# STM-Board-v1_0.net
KiCad netlist of a schematic drawn in Altium Designer
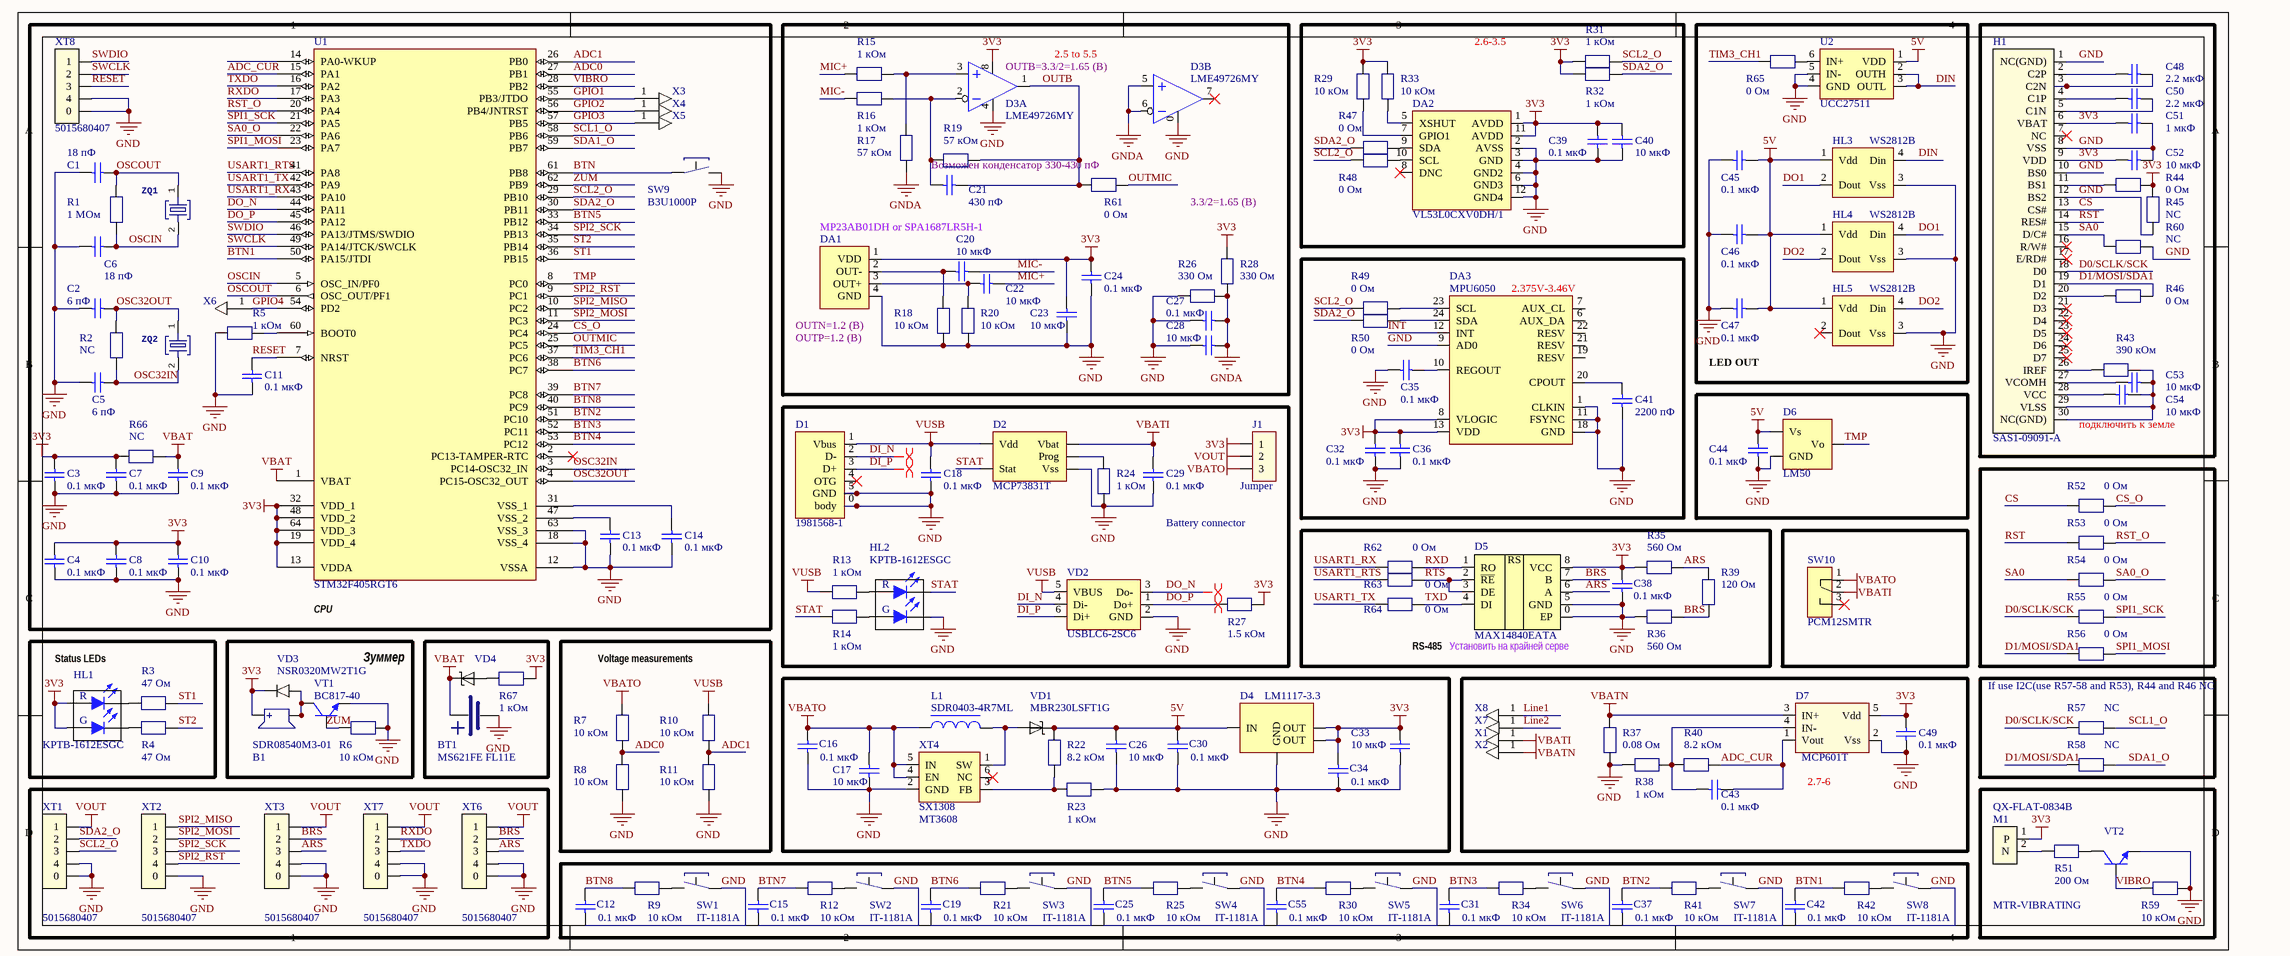
[diagram p0: STM-Board-v1.0.SchDoc]

(export (version "E")
  (design (tool "Eeschema 10.0.6"))
  (components
    (comp (ref "B1")
      (value "SDR08540M3-01")
      (footprint "SDR08540M3-01")
      (libsource (lib "dan") (part "SDR08540M3-01"))
    )
    (comp (ref "BT1")
      (value "MS621FE FL11E")
      (footprint "MS621FE FL11E")
      (libsource (lib "dan") (part "Battery RTC"))
    )
    (comp (ref "C1")
      (value "18 пФ")
      (footprint "C0402")
      (description "Чип конденсатор 0805")
      (fields (field (name "Comment") "Capacitor"))
      (libsource (lib "dan") (part "Capacitor"))
    )
    (comp (ref "C2")
      (value "6 пФ")
      (footprint "C0402")
      (description "Чип конденсатор 0805")
      (fields (field (name "Comment") "Capacitor"))
      (libsource (lib "dan") (part "Capacitor"))
    )
    (comp (ref "C3")
      (value "0.1 мкФ")
      (footprint "C0402")
      (description "Чип конденсатор 0805")
      (fields (field (name "Comment") "Capacitor"))
      (libsource (lib "dan") (part "Capacitor"))
    )
    (comp (ref "C4")
      (value "0.1 мкФ")
      (footprint "C0402")
      (description "Чип конденсатор 0805")
      (fields (field (name "Comment") "Capacitor"))
      (libsource (lib "dan") (part "Capacitor"))
    )
    (comp (ref "C5")
      (value "6 пФ")
      (footprint "C0402")
      (description "Чип конденсатор 0805")
      (fields (field (name "Comment") "Capacitor"))
      (libsource (lib "dan") (part "Capacitor"))
    )
    (comp (ref "C6")
      (value "18 пФ")
      (footprint "C0402")
      (description "Чип конденсатор 0805")
      (fields (field (name "Comment") "Capacitor"))
      (libsource (lib "dan") (part "Capacitor"))
    )
    (comp (ref "C7")
      (value "0.1 мкФ")
      (footprint "C0402")
      (description "Чип конденсатор 0805")
      (fields (field (name "Comment") "Capacitor"))
      (libsource (lib "dan") (part "Capacitor"))
    )
    (comp (ref "C8")
      (value "0.1 мкФ")
      (footprint "C0402")
      (description "Чип конденсатор 0805")
      (fields (field (name "Comment") "Capacitor"))
      (libsource (lib "dan") (part "Capacitor"))
    )
    (comp (ref "C9")
      (value "0.1 мкФ")
      (footprint "C0402")
      (description "Чип конденсатор 0805")
      (fields (field (name "Comment") "Capacitor"))
      (libsource (lib "dan") (part "Capacitor"))
    )
    (comp (ref "C10")
      (value "0.1 мкФ")
      (footprint "C0402")
      (description "Чип конденсатор 0805")
      (fields (field (name "Comment") "Capacitor"))
      (libsource (lib "dan") (part "Capacitor"))
    )
    (comp (ref "C11")
      (value "0.1 мкФ")
      (footprint "C0402")
      (description "Чип конденсатор 0805")
      (fields (field (name "Comment") "Capacitor"))
      (libsource (lib "dan") (part "Capacitor"))
    )
    (comp (ref "C12")
      (value "0.1 мкФ")
      (footprint "C0402")
      (description "Чип конденсатор 0805")
      (fields (field (name "Comment") "Capacitor"))
      (libsource (lib "dan") (part "Capacitor"))
    )
    (comp (ref "C13")
      (value "0.1 мкФ")
      (footprint "C0402")
      (description "Чип конденсатор 0805")
      (fields (field (name "Comment") "Capacitor"))
      (libsource (lib "dan") (part "Capacitor"))
    )
    (comp (ref "C14")
      (value "0.1 мкФ")
      (footprint "C0402")
      (description "Чип конденсатор 0805")
      (fields (field (name "Comment") "Capacitor"))
      (libsource (lib "dan") (part "Capacitor"))
    )
    (comp (ref "C15")
      (value "0.1 мкФ")
      (footprint "C0402")
      (description "Чип конденсатор 0805")
      (fields (field (name "Comment") "Capacitor"))
      (libsource (lib "dan") (part "Capacitor"))
    )
    (comp (ref "C16")
      (value "0.1 мкФ")
      (footprint "C0402")
      (description "Чип конденсатор 0805")
      (fields (field (name "Comment") "Capacitor"))
      (libsource (lib "dan") (part "Capacitor"))
    )
    (comp (ref "C17")
      (value "10 мкФ")
      (footprint "1206")
      (description "Чип конденсатор 0805")
      (fields (field (name "Comment") "Capacitor"))
      (libsource (lib "dan") (part "Capacitor"))
    )
    (comp (ref "C18")
      (value "0.1 мкФ")
      (footprint "C0402")
      (description "Чип конденсатор 0805")
      (fields (field (name "Comment") "Capacitor"))
      (libsource (lib "dan") (part "Capacitor"))
    )
    (comp (ref "C19")
      (value "0.1 мкФ")
      (footprint "C0402")
      (description "Чип конденсатор 0805")
      (fields (field (name "Comment") "Capacitor"))
      (libsource (lib "dan") (part "Capacitor"))
    )
    (comp (ref "C20")
      (value "10 мкФ")
      (footprint "C0402")
      (description "Чип конденсатор 0805")
      (fields (field (name "Comment") "Capacitor"))
      (libsource (lib "dan") (part "Capacitor"))
    )
    (comp (ref "C21")
      (value "430 пФ")
      (footprint "C0402")
      (description "Чип конденсатор 0805")
      (fields (field (name "Comment") "Capacitor"))
      (libsource (lib "dan") (part "Capacitor"))
    )
    (comp (ref "C22")
      (value "10 мкФ")
      (footprint "C0402")
      (description "Чип конденсатор 0805")
      (fields (field (name "Comment") "Capacitor"))
      (libsource (lib "dan") (part "Capacitor"))
    )
    (comp (ref "C23")
      (value "10 мкФ")
      (footprint "C0402")
      (description "Чип конденсатор 0805")
      (fields (field (name "Comment") "Capacitor"))
      (libsource (lib "dan") (part "Capacitor"))
    )
    (comp (ref "C24")
      (value "0.1 мкФ")
      (footprint "C0402")
      (description "Чип конденсатор 0805")
      (fields (field (name "Comment") "Capacitor"))
      (libsource (lib "dan") (part "Capacitor"))
    )
    (comp (ref "C25")
      (value "0.1 мкФ")
      (footprint "C0402")
      (description "Чип конденсатор 0805")
      (fields (field (name "Comment") "Capacitor"))
      (libsource (lib "dan") (part "Capacitor"))
    )
    (comp (ref "C26")
      (value "10 мкФ")
      (footprint "1206")
      (description "Чип конденсатор 0805")
      (fields (field (name "Comment") "Capacitor"))
      (libsource (lib "dan") (part "Capacitor"))
    )
    (comp (ref "C27")
      (value "0.1 мкФ")
      (footprint "C0402")
      (description "Чип конденсатор 0805")
      (fields (field (name "Comment") "Capacitor"))
      (libsource (lib "dan") (part "Capacitor"))
    )
    (comp (ref "C28")
      (value "10 мкФ")
      (footprint "C0402")
      (description "Чип конденсатор 0805")
      (fields (field (name "Comment") "Capacitor"))
      (libsource (lib "dan") (part "Capacitor"))
    )
    (comp (ref "C29")
      (value "0.1 мкФ")
      (footprint "C0402")
      (description "Чип конденсатор 0805")
      (fields (field (name "Comment") "Capacitor"))
      (libsource (lib "dan") (part "Capacitor"))
    )
    (comp (ref "C30")
      (value "0.1 мкФ")
      (footprint "C0402")
      (description "Чип конденсатор 0805")
      (fields (field (name "Comment") "Capacitor"))
      (libsource (lib "dan") (part "Capacitor"))
    )
    (comp (ref "C31")
      (value "0.1 мкФ")
      (footprint "C0402")
      (description "Чип конденсатор 0805")
      (fields (field (name "Comment") "Capacitor"))
      (libsource (lib "dan") (part "Capacitor"))
    )
    (comp (ref "C32")
      (value "0.1 мкФ")
      (footprint "C0402")
      (description "Чип конденсатор 0805")
      (fields (field (name "Comment") "Capacitor"))
      (libsource (lib "dan") (part "Capacitor"))
    )
    (comp (ref "C33")
      (value "10 мкФ")
      (footprint "1206")
      (description "Чип конденсатор 0805")
      (fields (field (name "Comment") "Capacitor"))
      (libsource (lib "dan") (part "Capacitor"))
    )
    (comp (ref "C34")
      (value "0.1 мкФ")
      (footprint "C0402")
      (description "Чип конденсатор 0805")
      (fields (field (name "Comment") "Capacitor"))
      (libsource (lib "dan") (part "Capacitor"))
    )
    (comp (ref "C35")
      (value "0.1 мкФ")
      (footprint "C0402")
      (description "Чип конденсатор 0805")
      (fields (field (name "Comment") "Capacitor"))
      (libsource (lib "dan") (part "Capacitor"))
    )
    (comp (ref "C36")
      (value "0.1 мкФ")
      (footprint "C0402")
      (description "Чип конденсатор 0805")
      (fields (field (name "Comment") "Capacitor"))
      (libsource (lib "dan") (part "Capacitor"))
    )
    (comp (ref "C37")
      (value "0.1 мкФ")
      (footprint "C0402")
      (description "Чип конденсатор 0805")
      (fields (field (name "Comment") "Capacitor"))
      (libsource (lib "dan") (part "Capacitor"))
    )
    (comp (ref "C38")
      (value "0.1 мкФ")
      (footprint "C0402")
      (description "Чип конденсатор 0805")
      (fields (field (name "Comment") "Capacitor"))
      (libsource (lib "dan") (part "Capacitor"))
    )
    (comp (ref "C39")
      (value "0.1 мкФ")
      (footprint "C0402")
      (description "Чип конденсатор 0805")
      (fields (field (name "Comment") "Capacitor"))
      (libsource (lib "dan") (part "Capacitor"))
    )
    (comp (ref "C40")
      (value "10 мкФ")
      (footprint "C0402")
      (description "Чип конденсатор 0805")
      (fields (field (name "Comment") "Capacitor"))
      (libsource (lib "dan") (part "Capacitor"))
    )
    (comp (ref "C41")
      (value "2200 пФ")
      (footprint "C0402")
      (description "Чип конденсатор 0805")
      (fields (field (name "Comment") "Capacitor"))
      (libsource (lib "dan") (part "Capacitor"))
    )
    (comp (ref "C42")
      (value "0.1 мкФ")
      (footprint "C0402")
      (description "Чип конденсатор 0805")
      (fields (field (name "Comment") "Capacitor"))
      (libsource (lib "dan") (part "Capacitor"))
    )
    (comp (ref "C43")
      (value "0.1 мкФ")
      (footprint "C0402")
      (description "Чип конденсатор 0805")
      (fields (field (name "Comment") "Capacitor"))
      (libsource (lib "dan") (part "Capacitor"))
    )
    (comp (ref "C44")
      (value "0.1 мкФ")
      (footprint "C0402")
      (description "Чип конденсатор 0805")
      (fields (field (name "Comment") "Capacitor"))
      (libsource (lib "dan") (part "Capacitor"))
    )
    (comp (ref "C45")
      (value "0.1 мкФ")
      (footprint "C0402")
      (description "Чип конденсатор 0805")
      (fields (field (name "Comment") "Capacitor"))
      (libsource (lib "dan") (part "Capacitor"))
    )
    (comp (ref "C46")
      (value "0.1 мкФ")
      (footprint "C0402")
      (description "Чип конденсатор 0805")
      (fields (field (name "Comment") "Capacitor"))
      (libsource (lib "dan") (part "Capacitor"))
    )
    (comp (ref "C47")
      (value "0.1 мкФ")
      (footprint "C0402")
      (description "Чип конденсатор 0805")
      (fields (field (name "Comment") "Capacitor"))
      (libsource (lib "dan") (part "Capacitor"))
    )
    (comp (ref "C48")
      (value "2.2 мкФ")
      (footprint "C0402")
      (description "Чип конденсатор 0805")
      (fields (field (name "Comment") "Capacitor"))
      (libsource (lib "dan") (part "Capacitor"))
    )
    (comp (ref "C49")
      (value "0.1 мкФ")
      (footprint "C0402")
      (description "Чип конденсатор 0805")
      (fields (field (name "Comment") "Capacitor"))
      (libsource (lib "dan") (part "Capacitor"))
    )
    (comp (ref "C50")
      (value "2.2 мкФ")
      (footprint "C0402")
      (description "Чип конденсатор 0805")
      (fields (field (name "Comment") "Capacitor"))
      (libsource (lib "dan") (part "Capacitor"))
    )
    (comp (ref "C51")
      (value "1 мкФ")
      (footprint "C0402")
      (description "Чип конденсатор 0805")
      (fields (field (name "Comment") "Capacitor"))
      (libsource (lib "dan") (part "Capacitor"))
    )
    (comp (ref "C52")
      (value "10 мкФ")
      (footprint "C0402")
      (description "Чип конденсатор 0805")
      (fields (field (name "Comment") "Capacitor"))
      (libsource (lib "dan") (part "Capacitor"))
    )
    (comp (ref "C53")
      (value "10 мкФ")
      (footprint "C0402")
      (description "Чип конденсатор 0805")
      (fields (field (name "Comment") "Capacitor"))
      (libsource (lib "dan") (part "Capacitor"))
    )
    (comp (ref "C54")
      (value "10 мкФ")
      (footprint "C0402")
      (description "Чип конденсатор 0805")
      (fields (field (name "Comment") "Capacitor"))
      (libsource (lib "dan") (part "Capacitor"))
    )
    (comp (ref "C55")
      (value "0.1 мкФ")
      (footprint "C0402")
      (description "Чип конденсатор 0805")
      (fields (field (name "Comment") "Capacitor"))
      (libsource (lib "dan") (part "Capacitor"))
    )
    (comp (ref "D1")
      (value "1981568-1")
      (footprint "MicroUSB-B")
      (description "micro")
      (libsource (lib "dan") (part "USB_micro"))
    )
    (comp (ref "D2") (value "MCP73831T") (footprint "SOT23-5") (libsource (lib "dan") (part "MCP73831")))
    (comp (ref "D3")
      (value "LME49726MY")
      (footprint "MSOP8 - PP")
      (description "Comparators")
      (fields (field (name "Comment") "Audio Operational Amplifier"))
      (libsource (lib "dan") (part "LME49726"))
    )
    (comp (ref "D4") (value "LM1117-3.3") (footprint "SOT223") (libsource (lib "dan") (part "LM1117")))
    (comp (ref "D5")
      (value "MAX14840EATA")
      (footprint "TDFN-8")
      (description "RS-485")
      (libsource (lib "dan") (part "MAX14840"))
    )
    (comp (ref "D6")
      (value "LM50")
      (footprint "SOT-23")
      (description "Temperatury sensors")
      (fields (field (name "Comment") "Датчик температуры"))
      (libsource (lib "dan") (part "LM50"))
    )
    (comp (ref "D7")
      (value "MCP601T")
      (footprint "SOT23-5")
      (fields (field (name "Comment") "Операционный усилитель"))
      (libsource (lib "dan") (part "MCP601T"))
    )
    (comp (ref "DA1")
      (value "MP23AB01DH or SPA1687LR5H-1")
      (footprint "MP23AB01DH")
      (libsource (lib "dan") (part "MP23AB01DH"))
    )
    (comp (ref "DA2")
      (value "VL53L0CXV0DH/1")
      (footprint "dan:VL53L0X - big")
      (fields (field (name "Comment") "ИК датчик VL53L0X"))
      (libsource (lib "dan") (part "VL53L0X"))
    )
    (comp (ref "DA3")
      (value "MPU6050")
      (footprint "MPU-6050")
      (fields (field (name "Comment") "Гироскоп"))
      (libsource (lib "dan") (part "MPU6050"))
    )
    (comp (ref "H1")
      (value "SAS1-09091-A")
      (footprint "OLED 1.3 128x64")
      (description "1.3in OLED 128x64  SAS1-09091-A")
      (fields (field (name "Comment") "OLED DIsp 1.3 128x64"))
      (libsource (lib "dan") (part "OLED_1.3_128x64"))
    )
    (comp (ref "HL1")
      (value "KPTB-1612ESGC")
      (footprint "LED_1.6x1.25")
      (libsource (lib "dan") (part "LED_x2_RG"))
    )
    (comp (ref "HL2")
      (value "KPTB-1612ESGC")
      (footprint "LED_1.6x1.25")
      (libsource (lib "dan") (part "LED_x2_RG"))
    )
    (comp (ref "HL3") (value "WS2812B") (footprint "WS2812B_N") (libsource (lib "dan") (part "WS2812B")))
    (comp (ref "HL4") (value "WS2812B") (footprint "WS2812B_N") (libsource (lib "dan") (part "WS2812B")))
    (comp (ref "HL5") (value "WS2812B") (footprint "WS2812B_N") (libsource (lib "dan") (part "WS2812B")))
    (comp (ref "J1")
      (value "Jumper")
      (footprint "Jumper_3")
      (fields (field (name "Comment") "Jumper_2"))
      (libsource (lib "dan") (part "Jumper_2"))
    )
    (comp (ref "L1") (value "SDR0403-4R7ML") (footprint "SDR0403") (libsource (lib "dan") (part "inductor")))
    (comp (ref "M1")
      (value "QX-FLAT-0834B")
      (footprint "QX-FLAT-0834B")
      (description "VIBRATING")
      (libsource (lib "dan") (part "QX-FLAT-0834B"))
    )
    (comp (ref "R1")
      (value "1 МОм")
      (footprint "R0402")
      (fields (field (name "Comment") "Чип резистор"))
      (libsource (lib "") (part "Resistor_2"))
    )
    (comp (ref "R2")
      (value "NC")
      (footprint "R0402")
      (fields (field (name "Comment") "Чип резистор"))
      (libsource (lib "") (part "Resistor_3"))
    )
    (comp (ref "R3")
      (value "47 Ом")
      (footprint "R0402")
      (fields (field (name "Comment") "Чип резистор 0402"))
      (libsource (lib "dan") (part "Resistor"))
    )
    (comp (ref "R4")
      (value "47 Ом")
      (footprint "R0402")
      (fields (field (name "Comment") "Чип резистор 0402"))
      (libsource (lib "dan") (part "Resistor"))
    )
    (comp (ref "R5")
      (value "1 кОм")
      (footprint "R0402")
      (fields (field (name "Comment") "Чип резистор"))
      (libsource (lib "") (part "Resistor_1"))
    )
    (comp (ref "R6")
      (value "10 кОм")
      (footprint "R0402")
      (fields (field (name "Comment") "Чип резистор"))
      (libsource (lib "") (part "Resistor_1"))
    )
    (comp (ref "R7")
      (value "10 кОм")
      (footprint "R0402")
      (fields (field (name "Comment") "Чип резистор"))
      (libsource (lib "") (part "Resistor_3"))
    )
    (comp (ref "R8")
      (value "10 кОм")
      (footprint "R0402")
      (fields (field (name "Comment") "Чип резистор"))
      (libsource (lib "") (part "Resistor_3"))
    )
    (comp (ref "R9")
      (value "10 кОм")
      (footprint "R0402")
      (fields (field (name "Comment") "Чип резистор"))
      (libsource (lib "dan") (part "Resistor"))
    )
    (comp (ref "R10")
      (value "10 кОм")
      (footprint "R0402")
      (fields (field (name "Comment") "Чип резистор"))
      (libsource (lib "") (part "Resistor_3"))
    )
    (comp (ref "R11")
      (value "10 кОм")
      (footprint "R0402")
      (fields (field (name "Comment") "Чип резистор"))
      (libsource (lib "") (part "Resistor_3"))
    )
    (comp (ref "R12")
      (value "10 кОм")
      (footprint "R0402")
      (fields (field (name "Comment") "Чип резистор"))
      (libsource (lib "dan") (part "Resistor"))
    )
    (comp (ref "R13")
      (value "1 кОм")
      (footprint "R0402")
      (description "Чип резистор 0402")
      (libsource (lib "dan") (part "R0402"))
    )
    (comp (ref "R14")
      (value "1 кОм")
      (footprint "R0402")
      (description "Чип резистор 0402")
      (libsource (lib "dan") (part "R0402"))
    )
    (comp (ref "R15")
      (value "1 кОм")
      (footprint "R0402")
      (fields (field (name "Comment") "Чип резистор"))
      (libsource (lib "dan") (part "Resistor"))
    )
    (comp (ref "R16")
      (value "1 кОм")
      (footprint "R0402")
      (fields (field (name "Comment") "Чип резистор"))
      (libsource (lib "dan") (part "Resistor"))
    )
    (comp (ref "R17")
      (value "57 кОм")
      (footprint "R0402")
      (fields (field (name "Comment") "Чип резистор"))
      (libsource (lib "") (part "Resistor_2"))
    )
    (comp (ref "R18")
      (value "10 кОм")
      (footprint "R0402")
      (fields (field (name "Comment") "Чип резистор"))
      (libsource (lib "") (part "Resistor_3"))
    )
    (comp (ref "R19")
      (value "57 кОм")
      (footprint "R0402")
      (fields (field (name "Comment") "Чип резистор"))
      (libsource (lib "dan") (part "Resistor"))
    )
    (comp (ref "R20")
      (value "10 кОм")
      (footprint "R0402")
      (fields (field (name "Comment") "Чип резистор"))
      (libsource (lib "") (part "Resistor_3"))
    )
    (comp (ref "R21")
      (value "10 кОм")
      (footprint "R0402")
      (fields (field (name "Comment") "Чип резистор"))
      (libsource (lib "dan") (part "Resistor"))
    )
    (comp (ref "R22")
      (value "8.2 кОм")
      (footprint "R0402")
      (description "Чип резистор 0402")
      (libsource (lib "") (part "R0402_1"))
    )
    (comp (ref "R23")
      (value "1 кОм")
      (footprint "R0402")
      (description "Чип резистор 0402")
      (libsource (lib "dan") (part "R0402"))
    )
    (comp (ref "R24")
      (value "1 кОм")
      (footprint "R0402")
      (fields (field (name "Comment") "Чип резистор"))
      (libsource (lib "") (part "Resistor_2"))
    )
    (comp (ref "R25")
      (value "10 кОм")
      (footprint "R0402")
      (fields (field (name "Comment") "Чип резистор"))
      (libsource (lib "dan") (part "Resistor"))
    )
    (comp (ref "R26")
      (value "330 Ом")
      (footprint "R0402")
      (fields (field (name "Comment") "Чип резистор"))
      (libsource (lib "dan") (part "Resistor"))
    )
    (comp (ref "R27")
      (value "1.5 кОм")
      (footprint "R0402")
      (fields (field (name "Comment") "Чип резистор"))
      (libsource (lib "dan") (part "Resistor"))
    )
    (comp (ref "R28")
      (value "330 Ом")
      (footprint "R0402")
      (fields (field (name "Comment") "Чип резистор"))
      (libsource (lib "") (part "Resistor_2"))
    )
    (comp (ref "R29")
      (value "10 кОм")
      (footprint "R0402")
      (fields (field (name "Comment") "Чип резистор"))
      (libsource (lib "") (part "Resistor_2"))
    )
    (comp (ref "R30")
      (value "10 кОм")
      (footprint "R0402")
      (fields (field (name "Comment") "Чип резистор"))
      (libsource (lib "dan") (part "Resistor"))
    )
    (comp (ref "R31")
      (value "1 кОм")
      (footprint "R0402")
      (fields (field (name "Comment") "Чип резистор"))
      (libsource (lib "") (part "Resistor_1"))
    )
    (comp (ref "R32")
      (value "1 кОм")
      (footprint "R0402")
      (fields (field (name "Comment") "Чип резистор"))
      (libsource (lib "") (part "Resistor_1"))
    )
    (comp (ref "R33")
      (value "10 кОм")
      (footprint "R0402")
      (fields (field (name "Comment") "Чип резистор"))
      (libsource (lib "") (part "Resistor_2"))
    )
    (comp (ref "R34")
      (value "10 кОм")
      (footprint "R0402")
      (fields (field (name "Comment") "Чип резистор"))
      (libsource (lib "dan") (part "Resistor"))
    )
    (comp (ref "R35")
      (value "560 Ом")
      (footprint "R0402")
      (fields (field (name "Comment") "Чип резистор"))
      (libsource (lib "") (part "Resistor_1"))
    )
    (comp (ref "R36")
      (value "560 Ом")
      (footprint "R0402")
      (fields (field (name "Comment") "Чип резистор"))
      (libsource (lib "") (part "Resistor_1"))
    )
    (comp (ref "R37")
      (value "0.08 Ом")
      (footprint "P1206")
      (fields (field (name "Comment") "Чип резистор"))
      (libsource (lib "") (part "Resistor_3"))
    )
    (comp (ref "R38")
      (value "1 кОм")
      (footprint "R0402")
      (fields (field (name "Comment") "Чип резистор"))
      (libsource (lib "") (part "Resistor_1"))
    )
    (comp (ref "R39")
      (value "120 Ом")
      (footprint "R0402")
      (fields (field (name "Comment") "Чип резистор"))
      (libsource (lib "") (part "Resistor_3"))
    )
    (comp (ref "R40")
      (value "8.2 кОм")
      (footprint "R0402")
      (fields (field (name "Comment") "Чип резистор"))
      (libsource (lib "") (part "Resistor_1"))
    )
    (comp (ref "R41")
      (value "10 кОм")
      (footprint "R0402")
      (fields (field (name "Comment") "Чип резистор"))
      (libsource (lib "dan") (part "Resistor"))
    )
    (comp (ref "R42")
      (value "10 кОм")
      (footprint "R0402")
      (fields (field (name "Comment") "Чип резистор"))
      (libsource (lib "dan") (part "Resistor"))
    )
    (comp (ref "R43")
      (value "390 кОм")
      (footprint "R0402")
      (fields (field (name "Comment") "Чип резистор"))
      (libsource (lib "") (part "Resistor_1"))
    )
    (comp (ref "R44")
      (value "0 Ом")
      (footprint "R0402")
      (fields (field (name "Comment") "Чип резистор"))
      (libsource (lib "") (part "Resistor_1"))
    )
    (comp (ref "R45")
      (value "NC")
      (footprint "R0402")
      (fields (field (name "Comment") "Чип резистор"))
      (libsource (lib "") (part "Resistor_3"))
    )
    (comp (ref "R46")
      (value "0 Ом")
      (footprint "R0402")
      (fields (field (name "Comment") "Чип резистор"))
      (libsource (lib "") (part "Resistor_1"))
    )
    (comp (ref "R47")
      (value "0 Ом")
      (footprint "R0402")
      (fields (field (name "Comment") "Чип резистор"))
      (libsource (lib "") (part "Resistor_1"))
    )
    (comp (ref "R48")
      (value "0 Ом")
      (footprint "R0402")
      (fields (field (name "Comment") "Чип резистор"))
      (libsource (lib "") (part "Resistor_1"))
    )
    (comp (ref "R49")
      (value "0 Ом")
      (footprint "R0402")
      (fields (field (name "Comment") "Чип резистор"))
      (libsource (lib "") (part "Resistor_1"))
    )
    (comp (ref "R50")
      (value "0 Ом")
      (footprint "R0402")
      (fields (field (name "Comment") "Чип резистор"))
      (libsource (lib "") (part "Resistor_1"))
    )
    (comp (ref "R51")
      (value "200 Ом")
      (footprint "R0402")
      (fields (field (name "Comment") "Чип резистор"))
      (libsource (lib "dan") (part "Resistor"))
    )
    (comp (ref "R52")
      (value "0 Ом")
      (footprint "R0402")
      (fields (field (name "Comment") "Чип резистор"))
      (libsource (lib "") (part "Resistor_1"))
    )
    (comp (ref "R53")
      (value "0 Ом")
      (footprint "R0402")
      (fields (field (name "Comment") "Чип резистор"))
      (libsource (lib "") (part "Resistor_1"))
    )
    (comp (ref "R54")
      (value "0 Ом")
      (footprint "R0402")
      (fields (field (name "Comment") "Чип резистор"))
      (libsource (lib "") (part "Resistor_1"))
    )
    (comp (ref "R55")
      (value "0 Ом")
      (footprint "R0402")
      (fields (field (name "Comment") "Чип резистор"))
      (libsource (lib "") (part "Resistor_1"))
    )
    (comp (ref "R56")
      (value "0 Ом")
      (footprint "R0402")
      (fields (field (name "Comment") "Чип резистор"))
      (libsource (lib "") (part "Resistor_1"))
    )
    (comp (ref "R57")
      (value "NC")
      (footprint "R0402")
      (fields (field (name "Comment") "Чип резистор"))
      (libsource (lib "") (part "Resistor_1"))
    )
    (comp (ref "R58")
      (value "NC")
      (footprint "R0402")
      (fields (field (name "Comment") "Чип резистор"))
      (libsource (lib "") (part "Resistor_1"))
    )
    (comp (ref "R59")
      (value "10 кОм")
      (footprint "R0402")
      (fields (field (name "Comment") "Чип резистор"))
      (libsource (lib "dan") (part "Resistor"))
    )
    (comp (ref "R60")
      (value "NC")
      (footprint "R0402")
      (fields (field (name "Comment") "Чип резистор"))
      (libsource (lib "") (part "Resistor_1"))
    )
    (comp (ref "R61")
      (value "0 Ом")
      (footprint "R0402")
      (fields (field (name "Comment") "Чип резистор"))
      (libsource (lib "") (part "Resistor_1"))
    )
    (comp (ref "R62")
      (value "0 Ом")
      (footprint "R0402")
      (fields (field (name "Comment") "Чип резистор"))
      (libsource (lib "") (part "Resistor_1"))
    )
    (comp (ref "R63")
      (value "0 Ом")
      (footprint "R0402")
      (fields (field (name "Comment") "Чип резистор"))
      (libsource (lib "") (part "Resistor_1"))
    )
    (comp (ref "R64")
      (value "0 Ом")
      (footprint "R0402")
      (fields (field (name "Comment") "Чип резистор"))
      (libsource (lib "") (part "Resistor_1"))
    )
    (comp (ref "R65")
      (value "0 Ом")
      (footprint "R0402")
      (fields (field (name "Comment") "Чип резистор"))
      (libsource (lib "") (part "Resistor_1"))
    )
    (comp (ref "R66")
      (value "NC")
      (footprint "R0402")
      (fields (field (name "Comment") "Чип резистор"))
      (libsource (lib "dan") (part "Resistor"))
    )
    (comp (ref "R67")
      (value "1 кОм")
      (footprint "R0402")
      (fields (field (name "Comment") "Чип резистор"))
      (libsource (lib "") (part "Resistor_1"))
    )
    (comp (ref "SW1") (value "IT-1181A") (footprint "SWT-1") (libsource (lib "dan") (part "SWT-1-1")))
    (comp (ref "SW2") (value "IT-1181A") (footprint "SWT-1") (libsource (lib "dan") (part "SWT-1-1")))
    (comp (ref "SW3") (value "IT-1181A") (footprint "SWT-1") (libsource (lib "dan") (part "SWT-1-1")))
    (comp (ref "SW4") (value "IT-1181A") (footprint "SWT-1") (libsource (lib "dan") (part "SWT-1-1")))
    (comp (ref "SW5") (value "IT-1181A") (footprint "SWT-1") (libsource (lib "dan") (part "SWT-1-1")))
    (comp (ref "SW6") (value "IT-1181A") (footprint "SWT-1") (libsource (lib "dan") (part "SWT-1-1")))
    (comp (ref "SW7") (value "IT-1181A") (footprint "SWT-1") (libsource (lib "dan") (part "SWT-1-1")))
    (comp (ref "SW8") (value "IT-1181A") (footprint "SWT-1") (libsource (lib "dan") (part "SWT-1-1")))
    (comp (ref "SW9") (value "B3U1000P") (footprint "B3U1000P") (libsource (lib "dan") (part "SWT-1_1")))
    (comp (ref "SW10") (value "PCM12SMTR") (footprint "PCM12SMTR") (libsource (lib "dan") (part "PCM12SMTR")))
    (comp (ref "U1")
      (value "STM32F405RGT6")
      (footprint "LQFP64_L")
      (description "STM32 ARM-Cortex M3 32-bit MCU, 128 kB")
      (fields (field (name "Comment") "STM32F302RCT6"))
      (libsource (lib "dan") (part "STM32F302R"))
    )
    (comp (ref "U2") (value "UCC27511") (footprint "SOT23-6") (libsource (lib "dan") (part "UCC27511")))
    (comp (ref "VD1")
      (value "MBR230LSFT1G")
      (footprint "SOD-123")
      (description "Diod schottki")
      (libsource (lib "dan") (part "MBR120LSFT1G"))
    )
    (comp (ref "VD2")
      (value "USBLC6-2SC6")
      (footprint "SOT23-6")
      (description "ESD")
      (libsource (lib "dan") (part "USBLC6-2SC6"))
    )
    (comp (ref "VD3")
      (value "NSR0320MW2T1G")
      (footprint "SOD-323")
      (description "Диод")
      (libsource (lib "dan") (part "diode"))
    )
    (comp (ref "VD4")
      (value "NSR0320MW2T1G")
      (footprint "SOD-323")
      (description "Diod schottki")
      (libsource (lib "dan") (part "MBR120LSFT1G"))
    )
    (comp (ref "VT1")
      (value "ВС817-40")
      (footprint "SOT-23")
      (description "BC817-40 NPN Транзистор")
      (libsource (lib "dan") (part "BC817-40"))
    )
    (comp (ref "VT2")
      (value "ВС817-40")
      (footprint "SOT-23")
      (description "BC817-40 NPN Транзистор")
      (libsource (lib "dan") (part "BC817-40"))
    )
    (comp (ref "X1") (value "~") (footprint "PAD_1X2") (libsource (lib "dan") (part "Pad")))
    (comp (ref "X2") (value "~") (footprint "PAD_1X2") (libsource (lib "dan") (part "Pad")))
    (comp (ref "X3") (value "~") (footprint "Pad_R2") (libsource (lib "dan") (part "Pad")))
    (comp (ref "X4") (value "~") (footprint "Pad_R2") (libsource (lib "dan") (part "Pad")))
    (comp (ref "X5") (value "~") (footprint "Pad_R2") (libsource (lib "dan") (part "Pad")))
    (comp (ref "X6") (value "~") (footprint "Pad_R2") (libsource (lib "dan") (part "Pad")))
    (comp (ref "X7") (value "~") (footprint "Pad_R2") (libsource (lib "dan") (part "Pad")))
    (comp (ref "X8") (value "~") (footprint "Pad_R2") (libsource (lib "dan") (part "Pad")))
    (comp (ref "XT1")
      (value "5015680407")
      (footprint "5015680407")
      (description "molex")
      (libsource (lib "dan") (part "5015680407"))
    )
    (comp (ref "XT2")
      (value "5015680407")
      (footprint "5015680407")
      (description "molex")
      (libsource (lib "dan") (part "5015680407"))
    )
    (comp (ref "XT3")
      (value "5015680407")
      (footprint "5015680407")
      (description "molex")
      (libsource (lib "dan") (part "5015680407"))
    )
    (comp (ref "XT4")
      (value "SX1308")
      (footprint "SOT23-6")
      (description "DC-DC Step_Up")
      (libsource (lib "dan") (part "SX1308"))
    )
    (comp (ref "XT6")
      (value "5015680407")
      (footprint "5015680407")
      (description "molex")
      (libsource (lib "dan") (part "5015680407"))
    )
    (comp (ref "XT7")
      (value "5015680407")
      (footprint "5015680407")
      (description "molex")
      (libsource (lib "dan") (part "5015680407"))
    )
    (comp (ref "XT8")
      (value "5015680407")
      (footprint "5015680407")
      (description "molex")
      (libsource (lib "dan") (part "5015680407"))
    )
    (comp (ref "ZQ1")
      (value "ABM3-8.000MHZ-D2Y-T")
      (footprint "ABM3")
      (description "SMD Quartz")
      (libsource (lib "dan") (part "ABM3"))
    )
    (comp (ref "ZQ2")
      (value "ABS07-120-32.768KHZ-T")
      (footprint "ABS07")
      (description "SMD Quartz")
      (libsource (lib "dan") (part "ABM3"))
    )
  )
  (nets
    (net (code "1") (name "/ADC0") (class "Default")
      (node (ref "R7") (pin "2") (pinfunction "2_2") (pintype "passive"))
      (node (ref "R8") (pin "1") (pinfunction "1_1") (pintype "passive"))
      (node (ref "U1") (pin "27") (pinfunction "PB1_27") (pintype "bidirectional"))
    )
    (net (code "2") (name "/ADC1") (class "Default")
      (node (ref "R10") (pin "2") (pinfunction "2_2") (pintype "passive"))
      (node (ref "R11") (pin "1") (pinfunction "1_1") (pintype "passive"))
      (node (ref "U1") (pin "26") (pinfunction "PB0_26") (pintype "bidirectional"))
    )
    (net (code "3") (name "/ADC_CUR") (class "Default")
      (node (ref "C43") (pin "1") (pinfunction "1_1") (pintype "passive"))
      (node (ref "D7") (pin "1") (pinfunction "Vout_1") (pintype "passive"))
      (node (ref "R40") (pin "1") (pinfunction "1_1") (pintype "passive"))
      (node (ref "U1") (pin "15") (pinfunction "PA1_15") (pintype "bidirectional"))
    )
    (net (code "4") (name "/ARS") (class "Default")
      (node (ref "D5") (pin "6") (pinfunction "A_6") (pintype "passive"))
      (node (ref "R35") (pin "1") (pinfunction "1_1") (pintype "passive"))
      (node (ref "R39") (pin "1") (pinfunction "1_1") (pintype "passive"))
      (node (ref "XT3") (pin "3") (pinfunction "3_3") (pintype "passive"))
      (node (ref "XT6") (pin "3") (pinfunction "3_3") (pintype "passive"))
    )
    (net (code "5") (name "/BRS") (class "Default")
      (node (ref "D5") (pin "7") (pinfunction "B_7") (pintype "passive"))
      (node (ref "R36") (pin "1") (pinfunction "1_1") (pintype "passive"))
      (node (ref "R39") (pin "2") (pinfunction "2_2") (pintype "passive"))
      (node (ref "XT3") (pin "2") (pinfunction "2_2") (pintype "passive"))
      (node (ref "XT6") (pin "2") (pinfunction "2_2") (pintype "passive"))
    )
    (net (code "6") (name "/BTN") (class "Default")
      (node (ref "SW9") (pin "1") (pinfunction "1_1") (pintype "passive"))
      (node (ref "U1") (pin "61") (pinfunction "PB8_61") (pintype "bidirectional"))
    )
    (net (code "7") (name "/BTN1") (class "Default")
      (node (ref "C42") (pin "2") (pinfunction "2_2") (pintype "passive"))
      (node (ref "R42") (pin "1") (pinfunction "1_1") (pintype "passive"))
      (node (ref "U1") (pin "50") (pinfunction "PA15/JTDI_50") (pintype "bidirectional"))
    )
    (net (code "8") (name "/BTN2") (class "Default")
      (node (ref "C37") (pin "2") (pinfunction "2_2") (pintype "passive"))
      (node (ref "R41") (pin "1") (pinfunction "1_1") (pintype "passive"))
      (node (ref "U1") (pin "51") (pinfunction "PC10_51") (pintype "bidirectional"))
    )
    (net (code "9") (name "/BTN3") (class "Default")
      (node (ref "C31") (pin "2") (pinfunction "2_2") (pintype "passive"))
      (node (ref "R34") (pin "1") (pinfunction "1_1") (pintype "passive"))
      (node (ref "U1") (pin "52") (pinfunction "PC11_52") (pintype "bidirectional"))
    )
    (net (code "10") (name "/BTN4") (class "Default")
      (node (ref "C55") (pin "2") (pinfunction "2_2") (pintype "passive"))
      (node (ref "R30") (pin "1") (pinfunction "1_1") (pintype "passive"))
      (node (ref "U1") (pin "53") (pinfunction "PC12_53") (pintype "bidirectional"))
    )
    (net (code "11") (name "/BTN5") (class "Default")
      (node (ref "C25") (pin "2") (pinfunction "2_2") (pintype "passive"))
      (node (ref "R25") (pin "1") (pinfunction "1_1") (pintype "passive"))
      (node (ref "U1") (pin "33") (pinfunction "PB12_33") (pintype "bidirectional"))
    )
    (net (code "12") (name "/BTN6") (class "Default")
      (node (ref "C19") (pin "2") (pinfunction "2_2") (pintype "passive"))
      (node (ref "R21") (pin "1") (pinfunction "1_1") (pintype "passive"))
      (node (ref "U1") (pin "38") (pinfunction "PC7_38") (pintype "bidirectional"))
    )
    (net (code "13") (name "/BTN7") (class "Default")
      (node (ref "C15") (pin "2") (pinfunction "2_2") (pintype "passive"))
      (node (ref "R12") (pin "1") (pinfunction "1_1") (pintype "passive"))
      (node (ref "U1") (pin "39") (pinfunction "PC8_39") (pintype "bidirectional"))
    )
    (net (code "14") (name "/BTN8") (class "Default")
      (node (ref "C12") (pin "2") (pinfunction "2_2") (pintype "passive"))
      (node (ref "R9") (pin "1") (pinfunction "1_1") (pintype "passive"))
      (node (ref "U1") (pin "40") (pinfunction "PC9_40") (pintype "bidirectional"))
    )
    (net (code "15") (name "/CS") (class "Default")
      (node (ref "H1") (pin "13") (pinfunction "CS#_13") (pintype "passive"))
      (node (ref "R52") (pin "2") (pinfunction "2_2") (pintype "passive"))
    )
    (net (code "16") (name "/CS_O") (class "Default")
      (node (ref "R52") (pin "1") (pinfunction "1_1") (pintype "passive"))
      (node (ref "U1") (pin "24") (pinfunction "PC4_24") (pintype "bidirectional"))
    )
    (net (code "17") (name "/D0{slash}SCLK{slash}SCK") (class "Default")
      (node (ref "H1") (pin "18") (pinfunction "D0_18") (pintype "passive"))
      (node (ref "R55") (pin "2") (pinfunction "2_2") (pintype "passive"))
      (node (ref "R57") (pin "2") (pinfunction "2_2") (pintype "passive"))
    )
    (net (code "18") (name "/D1{slash}MOSI{slash}SDA1") (class "Default")
      (node (ref "H1") (pin "19") (pinfunction "D1_19") (pintype "passive"))
      (node (ref "R46") (pin "1") (pinfunction "1_1") (pintype "passive"))
      (node (ref "R56") (pin "2") (pinfunction "2_2") (pintype "passive"))
      (node (ref "R58") (pin "2") (pinfunction "2_2") (pintype "passive"))
    )
    (net (code "19") (name "/DIN") (class "Default")
      (node (ref "HL3") (pin "4") (pinfunction "Din_4") (pintype "passive"))
      (node (ref "U2") (pin "2") (pinfunction "OUTH_2") (pintype "power_in"))
      (node (ref "U2") (pin "3") (pinfunction "OUTL_3") (pintype "power_in"))
    )
    (net (code "20") (name "/DI_N") (class "Default")
      (node (ref "D1") (pin "2") (pinfunction "D-_2") (pintype "passive"))
      (node (ref "VD2") (pin "4") (pinfunction "Di-_4") (pintype "power_in"))
    )
    (net (code "21") (name "/DI_P") (class "Default")
      (node (ref "D1") (pin "3") (pinfunction "D+_3") (pintype "passive"))
      (node (ref "VD2") (pin "6") (pinfunction "Di+_6") (pintype "passive"))
    )
    (net (code "22") (name "/DO1") (class "Default")
      (node (ref "HL3") (pin "2") (pinfunction "Dout_2") (pintype "passive"))
      (node (ref "HL4") (pin "4") (pinfunction "Din_4") (pintype "passive"))
    )
    (net (code "23") (name "/DO2") (class "Default")
      (node (ref "HL4") (pin "2") (pinfunction "Dout_2") (pintype "passive"))
      (node (ref "HL5") (pin "4") (pinfunction "Din_4") (pintype "passive"))
    )
    (net (code "24") (name "/DO_N") (class "Default")
      (node (ref "U1") (pin "44") (pinfunction "PA11_44") (pintype "bidirectional"))
      (node (ref "VD2") (pin "3") (pinfunction "Do-_3") (pintype "power_in"))
    )
    (net (code "25") (name "/DO_P") (class "Default")
      (node (ref "R27") (pin "1") (pinfunction "1_1") (pintype "passive"))
      (node (ref "U1") (pin "45") (pinfunction "PA12_45") (pintype "bidirectional"))
      (node (ref "VD2") (pin "1") (pinfunction "Do+_1") (pintype "power_in"))
    )
    (net (code "26") (name "/GPIO1") (class "Default")
      (node (ref "U1") (pin "55") (pinfunction "PB3/JTDO_55") (pintype "bidirectional"))
      (node (ref "X3") (pin "1") (pinfunction "1_1") (pintype "passive"))
    )
    (net (code "27") (name "/GPIO2") (class "Default")
      (node (ref "U1") (pin "56") (pinfunction "PB4/JNTRST_56") (pintype "bidirectional"))
      (node (ref "X4") (pin "1") (pinfunction "1_1") (pintype "passive"))
    )
    (net (code "28") (name "/GPIO3") (class "Default")
      (node (ref "U1") (pin "57") (pinfunction "PB5_57") (pintype "bidirectional"))
      (node (ref "X5") (pin "1") (pinfunction "1_1") (pintype "passive"))
    )
    (net (code "29") (name "/GPIO4") (class "Default")
      (node (ref "U1") (pin "54") (pinfunction "PD2_54") (pintype "bidirectional"))
      (node (ref "X6") (pin "1") (pinfunction "1_1") (pintype "passive"))
    )
    (net (code "30") (name "/INT") (class "Default")
      (node (ref "DA3") (pin "12") (pinfunction "INT_12") (pintype "passive"))
    )
    (net (code "31") (name "/Line1") (class "Default")
      (node (ref "X8") (pin "1") (pinfunction "1_1") (pintype "passive"))
    )
    (net (code "32") (name "/Line2") (class "Default")
      (node (ref "X7") (pin "1") (pinfunction "1_1") (pintype "passive"))
    )
    (net (code "33") (name "/MIC+") (class "Default")
      (node (ref "C22") (pin "1") (pinfunction "1_1") (pintype "passive"))
      (node (ref "R15") (pin "1") (pinfunction "1_1") (pintype "passive"))
    )
    (net (code "34") (name "/MIC-") (class "Default")
      (node (ref "C20") (pin "1") (pinfunction "1_1") (pintype "passive"))
      (node (ref "R16") (pin "1") (pinfunction "1_1") (pintype "passive"))
    )
    (net (code "35") (name "/OSC32IN") (class "Default")
      (node (ref "C5") (pin "2") (pinfunction "2_2") (pintype "passive"))
      (node (ref "R2") (pin "2") (pinfunction "2_2") (pintype "passive"))
      (node (ref "U1") (pin "3") (pinfunction "PC14-OSC32_IN_3") (pintype "bidirectional"))
      (node (ref "ZQ2") (pin "2") (pinfunction "2_2") (pintype "passive"))
    )
    (net (code "36") (name "/OSC32OUT") (class "Default")
      (node (ref "C2") (pin "2") (pinfunction "2_2") (pintype "passive"))
      (node (ref "R2") (pin "1") (pinfunction "1_1") (pintype "passive"))
      (node (ref "U1") (pin "4") (pinfunction "PC15-OSC32_OUT_4") (pintype "bidirectional"))
      (node (ref "ZQ2") (pin "1") (pinfunction "1_1") (pintype "passive"))
    )
    (net (code "37") (name "/OSCIN") (class "Default")
      (node (ref "C6") (pin "2") (pinfunction "2_2") (pintype "passive"))
      (node (ref "R1") (pin "1") (pinfunction "1_1") (pintype "passive"))
      (node (ref "U1") (pin "5") (pinfunction "OSC_IN/PF0_5") (pintype "input"))
      (node (ref "ZQ1") (pin "2") (pinfunction "2_2") (pintype "passive"))
    )
    (net (code "38") (name "/OSCOUT") (class "Default")
      (node (ref "C1") (pin "2") (pinfunction "2_2") (pintype "passive"))
      (node (ref "R1") (pin "2") (pinfunction "2_2") (pintype "passive"))
      (node (ref "U1") (pin "6") (pinfunction "OSC_OUT/PF1_6") (pintype "output"))
      (node (ref "ZQ1") (pin "1") (pinfunction "1_1") (pintype "passive"))
    )
    (net (code "39") (name "/OUTB") (class "Default")
      (node (ref "C21") (pin "1") (pinfunction "1_1") (pintype "passive"))
      (node (ref "D3") (pin "1") (pinfunction "1OUT_1") (pintype "passive"))
      (node (ref "R19") (pin "2") (pinfunction "2_2") (pintype "passive"))
      (node (ref "R61") (pin "2") (pinfunction "2_2") (pintype "passive"))
    )
    (net (code "40") (name "/OUTMIC") (class "Default")
      (node (ref "R61") (pin "1") (pinfunction "1_1") (pintype "passive"))
      (node (ref "U1") (pin "25") (pinfunction "PC5_25") (pintype "bidirectional"))
    )
    (net (code "41") (name "/RESET") (class "Default")
      (node (ref "C11") (pin "1") (pinfunction "1_1") (pintype "passive"))
      (node (ref "U1") (pin "7") (pinfunction "NRST_7") (pintype "bidirectional"))
      (node (ref "XT8") (pin "3") (pinfunction "3_3") (pintype "passive"))
    )
    (net (code "42") (name "/RST") (class "Default")
      (node (ref "H1") (pin "14") (pinfunction "RES#_14") (pintype "passive"))
      (node (ref "R53") (pin "2") (pinfunction "2_2") (pintype "passive"))
    )
    (net (code "43") (name "/RST_O") (class "Default")
      (node (ref "R53") (pin "1") (pinfunction "1_1") (pintype "passive"))
      (node (ref "U1") (pin "20") (pinfunction "PA4_20") (pintype "bidirectional"))
    )
    (net (code "44") (name "/RTS") (class "Default")
      (node (ref "D5") (pin "2") (pinfunction "~{RE}_2") (pintype "passive"))
      (node (ref "D5") (pin "3") (pinfunction "DE_3") (pintype "passive"))
      (node (ref "R63") (pin "1") (pinfunction "1_1") (pintype "passive"))
    )
    (net (code "45") (name "/RXD") (class "Default")
      (node (ref "D5") (pin "1") (pinfunction "RO_1") (pintype "passive"))
      (node (ref "R62") (pin "1") (pinfunction "1_1") (pintype "passive"))
    )
    (net (code "46") (name "/RXDO") (class "Default")
      (node (ref "U1") (pin "17") (pinfunction "PA3_17") (pintype "bidirectional"))
      (node (ref "XT7") (pin "2") (pinfunction "2_2") (pintype "passive"))
    )
    (net (code "47") (name "/SA0") (class "Default")
      (node (ref "H1") (pin "15") (pinfunction "D/C#_15") (pintype "passive"))
      (node (ref "R54") (pin "2") (pinfunction "2_2") (pintype "passive"))
      (node (ref "R60") (pin "2") (pinfunction "2_2") (pintype "passive"))
    )
    (net (code "48") (name "/SA0_O") (class "Default")
      (node (ref "R54") (pin "1") (pinfunction "1_1") (pintype "passive"))
      (node (ref "U1") (pin "22") (pinfunction "PA6_22") (pintype "bidirectional"))
    )
    (net (code "49") (name "/SCL1_O") (class "Default")
      (node (ref "R57") (pin "1") (pinfunction "1_1") (pintype "passive"))
      (node (ref "U1") (pin "58") (pinfunction "PB6_58") (pintype "bidirectional"))
    )
    (net (code "50") (name "/SCL2_O") (class "Default")
      (node (ref "R31") (pin "1") (pinfunction "1_1") (pintype "passive"))
      (node (ref "R48") (pin "2") (pinfunction "2_2") (pintype "passive"))
      (node (ref "R49") (pin "2") (pinfunction "2_2") (pintype "passive"))
      (node (ref "U1") (pin "29") (pinfunction "PB10_29") (pintype "bidirectional"))
      (node (ref "XT1") (pin "3") (pinfunction "3_3") (pintype "passive"))
    )
    (net (code "51") (name "/SDA1_O") (class "Default")
      (node (ref "R58") (pin "1") (pinfunction "1_1") (pintype "passive"))
      (node (ref "U1") (pin "59") (pinfunction "PB7_59") (pintype "bidirectional"))
    )
    (net (code "52") (name "/SDA2_O") (class "Default")
      (node (ref "R32") (pin "1") (pinfunction "1_1") (pintype "passive"))
      (node (ref "R47") (pin "2") (pinfunction "2_2") (pintype "passive"))
      (node (ref "R50") (pin "2") (pinfunction "2_2") (pintype "passive"))
      (node (ref "U1") (pin "30") (pinfunction "PB11_30") (pintype "bidirectional"))
      (node (ref "XT1") (pin "2") (pinfunction "2_2") (pintype "passive"))
    )
    (net (code "53") (name "/SPI1_MOSI") (class "Default")
      (node (ref "R56") (pin "1") (pinfunction "1_1") (pintype "passive"))
      (node (ref "U1") (pin "23") (pinfunction "PA7_23") (pintype "bidirectional"))
    )
    (net (code "54") (name "/SPI1_SCK") (class "Default")
      (node (ref "R55") (pin "1") (pinfunction "1_1") (pintype "passive"))
      (node (ref "U1") (pin "21") (pinfunction "PA5_21") (pintype "bidirectional"))
    )
    (net (code "55") (name "/SPI2_MISO") (class "Default")
      (node (ref "U1") (pin "10") (pinfunction "PC2_10") (pintype "bidirectional"))
      (node (ref "XT2") (pin "1") (pinfunction "1_1") (pintype "passive"))
    )
    (net (code "56") (name "/SPI2_MOSI") (class "Default")
      (node (ref "U1") (pin "11") (pinfunction "PC3_11") (pintype "bidirectional"))
      (node (ref "XT2") (pin "2") (pinfunction "2_2") (pintype "passive"))
    )
    (net (code "57") (name "/SPI2_RST") (class "Default")
      (node (ref "U1") (pin "9") (pinfunction "PC1_9") (pintype "bidirectional"))
      (node (ref "XT2") (pin "4") (pinfunction "4_4") (pintype "passive"))
    )
    (net (code "58") (name "/SPI2_SCK") (class "Default")
      (node (ref "U1") (pin "34") (pinfunction "PB13_34") (pintype "bidirectional"))
      (node (ref "XT2") (pin "3") (pinfunction "3_3") (pintype "passive"))
    )
    (net (code "59") (name "/ST1") (class "Default")
      (node (ref "R3") (pin "2") (pinfunction "2_2") (pintype "passive"))
      (node (ref "U1") (pin "36") (pinfunction "PB15_36") (pintype "bidirectional"))
    )
    (net (code "60") (name "/ST2") (class "Default")
      (node (ref "R4") (pin "2") (pinfunction "2_2") (pintype "passive"))
      (node (ref "U1") (pin "35") (pinfunction "PB14_35") (pintype "bidirectional"))
    )
    (net (code "61") (name "/STAT") (class "Default")
      (node (ref "D2") (pin "1") (pinfunction "Stat_1") (pintype "power_in"))
      (node (ref "HL2") (pin "2") (pinfunction "C_2") (pintype "passive"))
      (node (ref "R14") (pin "1") (pinfunction "1_1") (pintype "passive"))
    )
    (net (code "62") (name "/SWCLK") (class "Default")
      (node (ref "U1") (pin "49") (pinfunction "PA14/JTCK/SWCLK_49") (pintype "bidirectional"))
      (node (ref "XT8") (pin "2") (pinfunction "2_2") (pintype "passive"))
    )
    (net (code "63") (name "/SWDIO") (class "Default")
      (node (ref "U1") (pin "46") (pinfunction "PA13/JTMS/SWDIO_46") (pintype "bidirectional"))
      (node (ref "XT8") (pin "1") (pinfunction "1_1") (pintype "passive"))
    )
    (net (code "64") (name "/TIM3_CH1") (class "Default")
      (node (ref "R65") (pin "2") (pinfunction "2_2") (pintype "passive"))
      (node (ref "U1") (pin "37") (pinfunction "PC6_37") (pintype "bidirectional"))
    )
    (net (code "65") (name "/TMP") (class "Default")
      (node (ref "D6") (pin "2") (pinfunction "Vo_2") (pintype "passive"))
      (node (ref "U1") (pin "8") (pinfunction "PC0_8") (pintype "bidirectional"))
    )
    (net (code "66") (name "/TXD") (class "Default")
      (node (ref "D5") (pin "4") (pinfunction "DI_4") (pintype "passive"))
      (node (ref "R64") (pin "1") (pinfunction "1_1") (pintype "passive"))
    )
    (net (code "67") (name "/TXDO") (class "Default")
      (node (ref "U1") (pin "16") (pinfunction "PA2_16") (pintype "bidirectional"))
      (node (ref "XT7") (pin "3") (pinfunction "3_3") (pintype "passive"))
    )
    (net (code "68") (name "/USART1_RTS") (class "Default")
      (node (ref "R63") (pin "2") (pinfunction "2_2") (pintype "passive"))
      (node (ref "U1") (pin "41") (pinfunction "PA8_41") (pintype "bidirectional"))
    )
    (net (code "69") (name "/USART1_RX") (class "Default")
      (node (ref "R62") (pin "2") (pinfunction "2_2") (pintype "passive"))
      (node (ref "U1") (pin "43") (pinfunction "PA10_43") (pintype "bidirectional"))
    )
    (net (code "70") (name "/USART1_TX") (class "Default")
      (node (ref "R64") (pin "2") (pinfunction "2_2") (pintype "passive"))
      (node (ref "U1") (pin "42") (pinfunction "PA9_42") (pintype "bidirectional"))
    )
    (net (code "71") (name "/VIBRO") (class "Default")
      (node (ref "R59") (pin "1") (pinfunction "1_1") (pintype "passive"))
      (node (ref "U1") (pin "28") (pinfunction "PB2_28") (pintype "bidirectional"))
      (node (ref "VT2") (pin "1") (pinfunction "B_1") (pintype "passive"))
    )
    (net (code "72") (name "/ZUM") (class "Default")
      (node (ref "R6") (pin "2") (pinfunction "2_2") (pintype "passive"))
      (node (ref "U1") (pin "62") (pinfunction "PB9_62") (pintype "bidirectional"))
      (node (ref "VT1") (pin "1") (pinfunction "B_1") (pintype "passive"))
    )
    (net (code "73") (name "3V3") (class "Default")
      (node (ref "B1") (pin "1") (pinfunction "+_1") (pintype "passive"))
      (node (ref "C10") (pin "1") (pinfunction "1_1") (pintype "passive"))
      (node (ref "C23") (pin "2") (pinfunction "2_2") (pintype "passive"))
      (node (ref "C24") (pin "2") (pinfunction "2_2") (pintype "passive"))
      (node (ref "C3") (pin "1") (pinfunction "1_1") (pintype "passive"))
      (node (ref "C32") (pin "1") (pinfunction "1_1") (pintype "passive"))
      (node (ref "C33") (pin "2") (pinfunction "2_2") (pintype "passive"))
      (node (ref "C34") (pin "2") (pinfunction "2_2") (pintype "passive"))
      (node (ref "C36") (pin "1") (pinfunction "1_1") (pintype "passive"))
      (node (ref "C38") (pin "2") (pinfunction "2_2") (pintype "passive"))
      (node (ref "C39") (pin "1") (pinfunction "1_1") (pintype "passive"))
      (node (ref "C4") (pin "1") (pinfunction "1_1") (pintype "passive"))
      (node (ref "C40") (pin "1") (pinfunction "1_1") (pintype "passive"))
      (node (ref "C49") (pin "1") (pinfunction "1_1") (pintype "passive"))
      (node (ref "C51") (pin "1") (pinfunction "1_1") (pintype "passive"))
      (node (ref "C52") (pin "1") (pinfunction "1_1") (pintype "passive"))
      (node (ref "C7") (pin "1") (pinfunction "1_1") (pintype "passive"))
      (node (ref "C8") (pin "1") (pinfunction "1_1") (pintype "passive"))
      (node (ref "D3") (pin "8") (pinfunction "Vcc_8") (pintype "passive"))
      (node (ref "D4") (pin "2") (pinfunction "OUT_2") (pintype "passive"))
      (node (ref "D4") (pin "4") (pinfunction "OUT_4") (pintype "passive"))
      (node (ref "D5") (pin "8") (pinfunction "VCC_8") (pintype "passive"))
      (node (ref "D7") (pin "5") (pinfunction "Vdd_5") (pintype "passive"))
      (node (ref "DA1") (pin "1") (pinfunction "VDD_1") (pintype "passive"))
      (node (ref "DA2") (pin "1") (pinfunction "AVDD_1") (pintype "passive"))
      (node (ref "DA2") (pin "11") (pinfunction "AVDD_11") (pintype "passive"))
      (node (ref "DA3") (pin "13") (pinfunction "VDD_13") (pintype "passive"))
      (node (ref "DA3") (pin "8") (pinfunction "VLOGIC_8") (pintype "passive"))
      (node (ref "H1") (pin "6") (pinfunction "VBAT_6") (pintype "passive"))
      (node (ref "H1") (pin "9") (pinfunction "VDD_9") (pintype "passive"))
      (node (ref "HL1") (pin "1") (pinfunction "A_1") (pintype "passive"))
      (node (ref "HL1") (pin "3") (pinfunction "A_3") (pintype "passive"))
      (node (ref "J1") (pin "1") (pinfunction "1_1") (pintype "passive"))
      (node (ref "M1") (pin "1") (pinfunction "P_1") (pintype "passive"))
      (node (ref "R27") (pin "2") (pinfunction "2_2") (pintype "passive"))
      (node (ref "R28") (pin "2") (pinfunction "2_2") (pintype "passive"))
      (node (ref "R29") (pin "2") (pinfunction "2_2") (pintype "passive"))
      (node (ref "R31") (pin "2") (pinfunction "2_2") (pintype "passive"))
      (node (ref "R32") (pin "2") (pinfunction "2_2") (pintype "passive"))
      (node (ref "R33") (pin "2") (pinfunction "2_2") (pintype "passive"))
      (node (ref "R35") (pin "2") (pinfunction "2_2") (pintype "passive"))
      (node (ref "R44") (pin "1") (pinfunction "1_1") (pintype "passive"))
      (node (ref "R45") (pin "1") (pinfunction "1_1") (pintype "passive"))
      (node (ref "R66") (pin "1") (pinfunction "1_1") (pintype "passive"))
      (node (ref "R67") (pin "1") (pinfunction "1_1") (pintype "passive"))
      (node (ref "U1") (pin "13") (pinfunction "VDDA_13") (pintype "power_in"))
      (node (ref "U1") (pin "19") (pinfunction "VDD_4_19") (pintype "power_in"))
      (node (ref "U1") (pin "32") (pinfunction "VDD_1_32") (pintype "power_in"))
      (node (ref "U1") (pin "48") (pinfunction "VDD_2_48") (pintype "power_in"))
      (node (ref "U1") (pin "64") (pinfunction "VDD_3_64") (pintype "power_in"))
      (node (ref "VD3") (pin "1") (pinfunction "K_1") (pintype "passive"))
    )
    (net (code "74") (name "5V") (class "Default")
      (node (ref "C26") (pin "2") (pinfunction "2_2") (pintype "passive"))
      (node (ref "C30") (pin "2") (pinfunction "2_2") (pintype "passive"))
      (node (ref "C44") (pin "1") (pinfunction "1_1") (pintype "passive"))
      (node (ref "C45") (pin "2") (pinfunction "2_2") (pintype "passive"))
      (node (ref "C46") (pin "2") (pinfunction "2_2") (pintype "passive"))
      (node (ref "C47") (pin "2") (pinfunction "2_2") (pintype "passive"))
      (node (ref "D4") (pin "3") (pinfunction "IN_3") (pintype "passive"))
      (node (ref "D6") (pin "1") (pinfunction "Vs_1") (pintype "passive"))
      (node (ref "HL3") (pin "1") (pinfunction "Vdd_1") (pintype "passive"))
      (node (ref "HL4") (pin "1") (pinfunction "Vdd_1") (pintype "passive"))
      (node (ref "HL5") (pin "1") (pinfunction "Vdd_1") (pintype "passive"))
      (node (ref "R22") (pin "1") (pinfunction "1_1") (pintype "passive"))
      (node (ref "U2") (pin "1") (pinfunction "VDD_1") (pintype "power_in"))
      (node (ref "VD1") (pin "1") (pinfunction "K_1") (pintype "passive"))
    )
    (net (code "75") (name "GND") (class "Default")
      (node (ref "BT1") (pin "2") (pinfunction "-_2") (pintype "passive"))
      (node (ref "C1") (pin "1") (pinfunction "1_1") (pintype "passive"))
      (node (ref "C10") (pin "2") (pinfunction "2_2") (pintype "passive"))
      (node (ref "C11") (pin "2") (pinfunction "2_2") (pintype "passive"))
      (node (ref "C12") (pin "1") (pinfunction "1_1") (pintype "passive"))
      (node (ref "C13") (pin "2") (pinfunction "2_2") (pintype "passive"))
      (node (ref "C14") (pin "2") (pinfunction "2_2") (pintype "passive"))
      (node (ref "C15") (pin "1") (pinfunction "1_1") (pintype "passive"))
      (node (ref "C16") (pin "1") (pinfunction "1_1") (pintype "passive"))
      (node (ref "C17") (pin "1") (pinfunction "1_1") (pintype "passive"))
      (node (ref "C18") (pin "1") (pinfunction "1_1") (pintype "passive"))
      (node (ref "C19") (pin "1") (pinfunction "1_1") (pintype "passive"))
      (node (ref "C2") (pin "1") (pinfunction "1_1") (pintype "passive"))
      (node (ref "C23") (pin "1") (pinfunction "1_1") (pintype "passive"))
      (node (ref "C24") (pin "1") (pinfunction "1_1") (pintype "passive"))
      (node (ref "C25") (pin "1") (pinfunction "1_1") (pintype "passive"))
      (node (ref "C26") (pin "1") (pinfunction "1_1") (pintype "passive"))
      (node (ref "C27") (pin "2") (pinfunction "2_2") (pintype "passive"))
      (node (ref "C28") (pin "2") (pinfunction "2_2") (pintype "passive"))
      (node (ref "C29") (pin "1") (pinfunction "1_1") (pintype "passive"))
      (node (ref "C3") (pin "2") (pinfunction "2_2") (pintype "passive"))
      (node (ref "C30") (pin "1") (pinfunction "1_1") (pintype "passive"))
      (node (ref "C31") (pin "1") (pinfunction "1_1") (pintype "passive"))
      (node (ref "C32") (pin "2") (pinfunction "2_2") (pintype "passive"))
      (node (ref "C33") (pin "1") (pinfunction "1_1") (pintype "passive"))
      (node (ref "C34") (pin "1") (pinfunction "1_1") (pintype "passive"))
      (node (ref "C35") (pin "1") (pinfunction "1_1") (pintype "passive"))
      (node (ref "C36") (pin "2") (pinfunction "2_2") (pintype "passive"))
      (node (ref "C37") (pin "1") (pinfunction "1_1") (pintype "passive"))
      (node (ref "C38") (pin "1") (pinfunction "1_1") (pintype "passive"))
      (node (ref "C39") (pin "2") (pinfunction "2_2") (pintype "passive"))
      (node (ref "C4") (pin "2") (pinfunction "2_2") (pintype "passive"))
      (node (ref "C40") (pin "2") (pinfunction "2_2") (pintype "passive"))
      (node (ref "C41") (pin "2") (pinfunction "2_2") (pintype "passive"))
      (node (ref "C42") (pin "1") (pinfunction "1_1") (pintype "passive"))
      (node (ref "C44") (pin "2") (pinfunction "2_2") (pintype "passive"))
      (node (ref "C45") (pin "1") (pinfunction "1_1") (pintype "passive"))
      (node (ref "C46") (pin "1") (pinfunction "1_1") (pintype "passive"))
      (node (ref "C47") (pin "1") (pinfunction "1_1") (pintype "passive"))
      (node (ref "C49") (pin "2") (pinfunction "2_2") (pintype "passive"))
      (node (ref "C5") (pin "1") (pinfunction "1_1") (pintype "passive"))
      (node (ref "C51") (pin "2") (pinfunction "2_2") (pintype "passive"))
      (node (ref "C52") (pin "2") (pinfunction "2_2") (pintype "passive"))
      (node (ref "C55") (pin "1") (pinfunction "1_1") (pintype "passive"))
      (node (ref "C6") (pin "1") (pinfunction "1_1") (pintype "passive"))
      (node (ref "C7") (pin "2") (pinfunction "2_2") (pintype "passive"))
      (node (ref "C8") (pin "2") (pinfunction "2_2") (pintype "passive"))
      (node (ref "C9") (pin "2") (pinfunction "2_2") (pintype "passive"))
      (node (ref "D1") (pin "0") (pinfunction "body_0") (pintype "passive"))
      (node (ref "D1") (pin "5") (pinfunction "GND_5") (pintype "passive"))
      (node (ref "D2") (pin "2") (pinfunction "Vss_2") (pintype "power_in"))
      (node (ref "D3") (pin "0") (pinfunction "PP_0") (pintype "passive"))
      (node (ref "D3") (pin "4") (pinfunction "GND_4") (pintype "passive"))
      (node (ref "D4") (pin "1") (pinfunction "GND_1") (pintype "passive"))
      (node (ref "D5") (pin "0") (pinfunction "EP_0") (pintype "passive"))
      (node (ref "D5") (pin "5") (pinfunction "GND_5") (pintype "passive"))
      (node (ref "D6") (pin "3") (pinfunction "GND_3") (pintype "passive"))
      (node (ref "D7") (pin "2") (pinfunction "Vss_2") (pintype "passive"))
      (node (ref "DA1") (pin "4") (pinfunction "GND_4") (pintype "passive"))
      (node (ref "DA2") (pin "12") (pinfunction "GND4_12") (pintype "passive"))
      (node (ref "DA2") (pin "2") (pinfunction "AVSS_2") (pintype "passive"))
      (node (ref "DA2") (pin "3") (pinfunction "GND_3") (pintype "passive"))
      (node (ref "DA2") (pin "4") (pinfunction "GND2_4") (pintype "passive"))
      (node (ref "DA2") (pin "6") (pinfunction "GND3_6") (pintype "passive"))
      (node (ref "DA3") (pin "1") (pinfunction "CLKIN_1") (pintype "passive"))
      (node (ref "DA3") (pin "11") (pinfunction "FSYNC_11") (pintype "passive"))
      (node (ref "DA3") (pin "18") (pinfunction "GND_18") (pintype "passive"))
      (node (ref "DA3") (pin "9") (pinfunction "AD0_9") (pintype "passive"))
      (node (ref "H1") (pin "1") (pinfunction "NC(GND)_1") (pintype "passive"))
      (node (ref "H1") (pin "10") (pinfunction "BS0_10") (pintype "passive"))
      (node (ref "H1") (pin "12") (pinfunction "BS2_12") (pintype "passive"))
      (node (ref "H1") (pin "8") (pinfunction "VSS_8") (pintype "passive"))
      (node (ref "HL2") (pin "4") (pinfunction "C_4") (pintype "passive"))
      (node (ref "HL3") (pin "3") (pinfunction "Vss_3") (pintype "passive"))
      (node (ref "HL4") (pin "3") (pinfunction "Vss_3") (pintype "passive"))
      (node (ref "HL5") (pin "3") (pinfunction "Vss_3") (pintype "passive"))
      (node (ref "R11") (pin "2") (pinfunction "2_2") (pintype "passive"))
      (node (ref "R18") (pin "2") (pinfunction "2_2") (pintype "passive"))
      (node (ref "R20") (pin "2") (pinfunction "2_2") (pintype "passive"))
      (node (ref "R23") (pin "2") (pinfunction "2_2") (pintype "passive"))
      (node (ref "R24") (pin "1") (pinfunction "1_1") (pintype "passive"))
      (node (ref "R26") (pin "1") (pinfunction "1_1") (pintype "passive"))
      (node (ref "R36") (pin "2") (pinfunction "2_2") (pintype "passive"))
      (node (ref "R37") (pin "2") (pinfunction "2_2") (pintype "passive"))
      (node (ref "R38") (pin "2") (pinfunction "2_2") (pintype "passive"))
      (node (ref "R45") (pin "2") (pinfunction "2_2") (pintype "passive"))
      (node (ref "R5") (pin "2") (pinfunction "2_2") (pintype "passive"))
      (node (ref "R59") (pin "2") (pinfunction "2_2") (pintype "passive"))
      (node (ref "R6") (pin "1") (pinfunction "1_1") (pintype "passive"))
      (node (ref "R60") (pin "1") (pinfunction "1_1") (pintype "passive"))
      (node (ref "R8") (pin "2") (pinfunction "2_2") (pintype "passive"))
      (node (ref "SW1") (pin "1") (pinfunction "1_1") (pintype "passive"))
      (node (ref "SW2") (pin "1") (pinfunction "1_1") (pintype "passive"))
      (node (ref "SW3") (pin "1") (pinfunction "1_1") (pintype "passive"))
      (node (ref "SW4") (pin "1") (pinfunction "1_1") (pintype "passive"))
      (node (ref "SW5") (pin "1") (pinfunction "1_1") (pintype "passive"))
      (node (ref "SW6") (pin "1") (pinfunction "1_1") (pintype "passive"))
      (node (ref "SW7") (pin "1") (pinfunction "1_1") (pintype "passive"))
      (node (ref "SW8") (pin "1") (pinfunction "1_1") (pintype "passive"))
      (node (ref "SW9") (pin "2") (pinfunction "2_2") (pintype "passive"))
      (node (ref "U1") (pin "12") (pinfunction "VSSA_12") (pintype "power_in"))
      (node (ref "U1") (pin "18") (pinfunction "VSS_4_18") (pintype "power_in"))
      (node (ref "U1") (pin "63") (pinfunction "VSS_3_63") (pintype "power_in"))
      (node (ref "U2") (pin "4") (pinfunction "GND_4") (pintype "power_in"))
      (node (ref "U2") (pin "5") (pinfunction "IN-_5") (pintype "power_in"))
      (node (ref "VD2") (pin "2") (pinfunction "GND_2") (pintype "power_in"))
      (node (ref "VT1") (pin "2") (pinfunction "E_2") (pintype "passive"))
      (node (ref "VT2") (pin "2") (pinfunction "E_2") (pintype "passive"))
      (node (ref "XT1") (pin "0") (pinfunction "0_0") (pintype "passive"))
      (node (ref "XT1") (pin "4") (pinfunction "4_4") (pintype "passive"))
      (node (ref "XT2") (pin "0") (pinfunction "0_0") (pintype "passive"))
      (node (ref "XT3") (pin "0") (pinfunction "0_0") (pintype "passive"))
      (node (ref "XT3") (pin "4") (pinfunction "4_4") (pintype "passive"))
      (node (ref "XT4") (pin "2") (pinfunction "GND_2") (pintype "passive"))
      (node (ref "XT6") (pin "0") (pinfunction "0_0") (pintype "passive"))
      (node (ref "XT6") (pin "4") (pinfunction "4_4") (pintype "passive"))
      (node (ref "XT7") (pin "0") (pinfunction "0_0") (pintype "passive"))
      (node (ref "XT7") (pin "4") (pinfunction "4_4") (pintype "passive"))
      (node (ref "XT8") (pin "0") (pinfunction "0_0") (pintype "passive"))
      (node (ref "XT8") (pin "4") (pinfunction "4_4") (pintype "passive"))
    )
    (net (code "76") (name "GNDA") (class "Default")
      (node (ref "C27") (pin "1") (pinfunction "1_1") (pintype "passive"))
      (node (ref "C28") (pin "1") (pinfunction "1_1") (pintype "passive"))
      (node (ref "D3") (pin "5") (pinfunction "2IN+_5") (pintype "passive"))
      (node (ref "D3") (pin "6") (pinfunction "2IN-_6") (pintype "passive"))
      (node (ref "R17") (pin "1") (pinfunction "1_1") (pintype "passive"))
      (node (ref "R26") (pin "2") (pinfunction "2_2") (pintype "passive"))
      (node (ref "R28") (pin "1") (pinfunction "1_1") (pintype "passive"))
    )
    (net (code "77") (name "Net-(D2-Prog)") (class "Default")
      (node (ref "D2") (pin "5") (pinfunction "Prog_5") (pintype "power_in"))
      (node (ref "R24") (pin "2") (pinfunction "2_2") (pintype "passive"))
    )
    (net (code "78") (name "Net-(D3A-1IN+)") (class "Default")
      (node (ref "D3") (pin "3") (pinfunction "1IN+_3") (pintype "passive"))
      (node (ref "R15") (pin "2") (pinfunction "2_2") (pintype "passive"))
      (node (ref "R17") (pin "2") (pinfunction "2_2") (pintype "passive"))
    )
    (net (code "79") (name "Net-(D3A-1IN-)") (class "Default")
      (node (ref "C21") (pin "2") (pinfunction "2_2") (pintype "passive"))
      (node (ref "D3") (pin "2") (pinfunction "1IN-_2") (pintype "passive"))
      (node (ref "R16") (pin "2") (pinfunction "2_2") (pintype "passive"))
      (node (ref "R19") (pin "1") (pinfunction "1_1") (pintype "passive"))
    )
    (net (code "80") (name "Net-(D7-IN-)") (class "Default")
      (node (ref "C43") (pin "2") (pinfunction "2_2") (pintype "passive"))
      (node (ref "D7") (pin "4") (pinfunction "IN-_4") (pintype "passive"))
      (node (ref "R38") (pin "1") (pinfunction "1_1") (pintype "passive"))
      (node (ref "R40") (pin "2") (pinfunction "2_2") (pintype "passive"))
    )
    (net (code "81") (name "Net-(DA1-OUT+)") (class "Default")
      (node (ref "C22") (pin "2") (pinfunction "2_2") (pintype "passive"))
      (node (ref "DA1") (pin "3") (pinfunction "OUT+_3") (pintype "passive"))
      (node (ref "R20") (pin "1") (pinfunction "1_1") (pintype "passive"))
    )
    (net (code "82") (name "Net-(DA1-OUT-)") (class "Default")
      (node (ref "C20") (pin "2") (pinfunction "2_2") (pintype "passive"))
      (node (ref "DA1") (pin "2") (pinfunction "OUT-_2") (pintype "passive"))
      (node (ref "R18") (pin "1") (pinfunction "1_1") (pintype "passive"))
    )
    (net (code "83") (name "Net-(DA2-GPIO1)") (class "Default")
      (node (ref "DA2") (pin "7") (pinfunction "GPIO1_7") (pintype "passive"))
      (node (ref "R29") (pin "1") (pinfunction "1_1") (pintype "passive"))
    )
    (net (code "84") (name "Net-(DA2-SCL)") (class "Default")
      (node (ref "DA2") (pin "10") (pinfunction "SCL_10") (pintype "passive"))
      (node (ref "R48") (pin "1") (pinfunction "1_1") (pintype "passive"))
    )
    (net (code "85") (name "Net-(DA2-SDA)") (class "Default")
      (node (ref "DA2") (pin "9") (pinfunction "SDA_9") (pintype "passive"))
      (node (ref "R47") (pin "1") (pinfunction "1_1") (pintype "passive"))
    )
    (net (code "86") (name "Net-(DA2-XSHUT)") (class "Default")
      (node (ref "DA2") (pin "5") (pinfunction "XSHUT_5") (pintype "passive"))
      (node (ref "R33") (pin "1") (pinfunction "1_1") (pintype "passive"))
    )
    (net (code "87") (name "Net-(DA3-CPOUT)") (class "Default")
      (node (ref "C41") (pin "1") (pinfunction "1_1") (pintype "passive"))
      (node (ref "DA3") (pin "20") (pinfunction "CPOUT_20") (pintype "passive"))
    )
    (net (code "88") (name "Net-(DA3-REGOUT)") (class "Default")
      (node (ref "C35") (pin "2") (pinfunction "2_2") (pintype "passive"))
      (node (ref "DA3") (pin "10") (pinfunction "REGOUT_10") (pintype "passive"))
    )
    (net (code "89") (name "Net-(DA3-SCL)") (class "Default")
      (node (ref "DA3") (pin "23") (pinfunction "SCL_23") (pintype "passive"))
      (node (ref "R49") (pin "1") (pinfunction "1_1") (pintype "passive"))
    )
    (net (code "90") (name "Net-(DA3-SDA)") (class "Default")
      (node (ref "DA3") (pin "24") (pinfunction "SDA_24") (pintype "passive"))
      (node (ref "R50") (pin "1") (pinfunction "1_1") (pintype "passive"))
    )
    (net (code "91") (name "Net-(H1-BS1)") (class "Default")
      (node (ref "H1") (pin "11") (pinfunction "BS1_11") (pintype "passive"))
      (node (ref "R44") (pin "2") (pinfunction "2_2") (pintype "passive"))
    )
    (net (code "92") (name "Net-(H1-C1N)") (class "Default")
      (node (ref "C50") (pin "2") (pinfunction "2_2") (pintype "passive"))
      (node (ref "H1") (pin "5") (pinfunction "C1N_5") (pintype "passive"))
    )
    (net (code "93") (name "Net-(H1-C1P)") (class "Default")
      (node (ref "C50") (pin "1") (pinfunction "1_1") (pintype "passive"))
      (node (ref "H1") (pin "4") (pinfunction "C1P_4") (pintype "passive"))
    )
    (net (code "94") (name "Net-(H1-C2N)") (class "Default")
      (node (ref "C48") (pin "2") (pinfunction "2_2") (pintype "passive"))
      (node (ref "H1") (pin "3") (pinfunction "C2N_3") (pintype "passive"))
    )
    (net (code "95") (name "Net-(H1-C2P)") (class "Default")
      (node (ref "C48") (pin "1") (pinfunction "1_1") (pintype "passive"))
      (node (ref "H1") (pin "2") (pinfunction "C2P_2") (pintype "passive"))
    )
    (net (code "96") (name "Net-(H1-D2)") (class "Default")
      (node (ref "H1") (pin "20") (pinfunction "D2_20") (pintype "passive"))
      (node (ref "R46") (pin "2") (pinfunction "2_2") (pintype "passive"))
    )
    (net (code "97") (name "Net-(H1-IREF)") (class "Default")
      (node (ref "H1") (pin "26") (pinfunction "IREF_26") (pintype "passive"))
      (node (ref "R43") (pin "2") (pinfunction "2_2") (pintype "passive"))
    )
    (net (code "98") (name "Net-(H1-VCC)") (class "Default")
      (node (ref "C54") (pin "1") (pinfunction "1_1") (pintype "passive"))
      (node (ref "H1") (pin "28") (pinfunction "VCC_28") (pintype "passive"))
    )
    (net (code "99") (name "Net-(H1-VCOMH)") (class "Default")
      (node (ref "C53") (pin "1") (pinfunction "1_1") (pintype "passive"))
      (node (ref "H1") (pin "27") (pinfunction "VCOMH_27") (pintype "passive"))
    )
    (net (code "100") (name "Net-(H1-VLSS)") (class "Default")
      (node (ref "C53") (pin "2") (pinfunction "2_2") (pintype "passive"))
      (node (ref "C54") (pin "2") (pinfunction "2_2") (pintype "passive"))
      (node (ref "H1") (pin "29") (pinfunction "VLSS_29") (pintype "passive"))
      (node (ref "H1") (pin "30") (pinfunction "NC(GND)_30") (pintype "passive"))
      (node (ref "R43") (pin "1") (pinfunction "1_1") (pintype "passive"))
    )
    (net (code "101") (name "Net-(HL1-C-Pad2)") (class "Default")
      (node (ref "HL1") (pin "2") (pinfunction "C_2") (pintype "passive"))
      (node (ref "R3") (pin "1") (pinfunction "1_1") (pintype "passive"))
    )
    (net (code "102") (name "Net-(HL1-C-Pad4)") (class "Default")
      (node (ref "HL1") (pin "4") (pinfunction "C_4") (pintype "passive"))
      (node (ref "R4") (pin "1") (pinfunction "1_1") (pintype "passive"))
    )
    (net (code "103") (name "Net-(HL2-A-Pad1)") (class "Default")
      (node (ref "HL2") (pin "1") (pinfunction "A_1") (pintype "passive"))
      (node (ref "R13") (pin "2") (pinfunction "2_2") (pintype "passive"))
    )
    (net (code "104") (name "Net-(HL2-A-Pad3)") (class "Default")
      (node (ref "HL2") (pin "3") (pinfunction "A_3") (pintype "passive"))
      (node (ref "R14") (pin "2") (pinfunction "2_2") (pintype "passive"))
    )
    (net (code "105") (name "Net-(M1-N)") (class "Default")
      (node (ref "M1") (pin "2") (pinfunction "N_2") (pintype "passive"))
      (node (ref "R51") (pin "1") (pinfunction "1_1") (pintype "passive"))
    )
    (net (code "106") (name "Net-(R9-Pad2)") (class "Default")
      (node (ref "R9") (pin "2") (pinfunction "2_2") (pintype "passive"))
      (node (ref "SW1") (pin "2") (pinfunction "2_2") (pintype "passive"))
    )
    (net (code "107") (name "Net-(R12-Pad2)") (class "Default")
      (node (ref "R12") (pin "2") (pinfunction "2_2") (pintype "passive"))
      (node (ref "SW2") (pin "2") (pinfunction "2_2") (pintype "passive"))
    )
    (net (code "108") (name "Net-(R21-Pad2)") (class "Default")
      (node (ref "R21") (pin "2") (pinfunction "2_2") (pintype "passive"))
      (node (ref "SW3") (pin "2") (pinfunction "2_2") (pintype "passive"))
    )
    (net (code "109") (name "Net-(R25-Pad2)") (class "Default")
      (node (ref "R25") (pin "2") (pinfunction "2_2") (pintype "passive"))
      (node (ref "SW4") (pin "2") (pinfunction "2_2") (pintype "passive"))
    )
    (net (code "110") (name "Net-(R30-Pad2)") (class "Default")
      (node (ref "R30") (pin "2") (pinfunction "2_2") (pintype "passive"))
      (node (ref "SW5") (pin "2") (pinfunction "2_2") (pintype "passive"))
    )
    (net (code "111") (name "Net-(R34-Pad2)") (class "Default")
      (node (ref "R34") (pin "2") (pinfunction "2_2") (pintype "passive"))
      (node (ref "SW6") (pin "2") (pinfunction "2_2") (pintype "passive"))
    )
    (net (code "112") (name "Net-(R41-Pad2)") (class "Default")
      (node (ref "R41") (pin "2") (pinfunction "2_2") (pintype "passive"))
      (node (ref "SW7") (pin "2") (pinfunction "2_2") (pintype "passive"))
    )
    (net (code "113") (name "Net-(R42-Pad2)") (class "Default")
      (node (ref "R42") (pin "2") (pinfunction "2_2") (pintype "passive"))
      (node (ref "SW8") (pin "2") (pinfunction "2_2") (pintype "passive"))
    )
    (net (code "114") (name "Net-(U1-BOOT0)") (class "Default")
      (node (ref "R5") (pin "1") (pinfunction "1_1") (pintype "passive"))
      (node (ref "U1") (pin "60") (pinfunction "BOOT0_60") (pintype "input"))
    )
    (net (code "115") (name "Net-(U1-VSS_1)") (class "Default")
      (node (ref "C14") (pin "1") (pinfunction "1_1") (pintype "passive"))
      (node (ref "U1") (pin "31") (pinfunction "VSS_1_31") (pintype "power_in"))
    )
    (net (code "116") (name "Net-(U1-VSS_2)") (class "Default")
      (node (ref "C13") (pin "1") (pinfunction "1_1") (pintype "passive"))
      (node (ref "U1") (pin "47") (pinfunction "VSS_2_47") (pintype "power_in"))
    )
    (net (code "117") (name "Net-(U2-IN+)") (class "Default")
      (node (ref "R65") (pin "1") (pinfunction "1_1") (pintype "passive"))
      (node (ref "U2") (pin "6") (pinfunction "IN+_6") (pintype "power_in"))
    )
    (net (code "118") (name "Net-(VD1-A)") (class "Default")
      (node (ref "L1") (pin "2") (pinfunction "2_2") (pintype "passive"))
      (node (ref "VD1") (pin "2") (pinfunction "A_2") (pintype "passive"))
      (node (ref "XT4") (pin "1") (pinfunction "SW_1") (pintype "passive"))
    )
    (net (code "119") (name "Net-(VD3-A)") (class "Default")
      (node (ref "B1") (pin "2") (pinfunction "-_2") (pintype "passive"))
      (node (ref "B1") (pin "3") (pinfunction "-_3") (pintype "passive"))
      (node (ref "B1") (pin "4") (pinfunction "-_4") (pintype "passive"))
      (node (ref "VD3") (pin "2") (pinfunction "A_2") (pintype "passive"))
      (node (ref "VT1") (pin "3") (pinfunction "C_3") (pintype "passive"))
    )
    (net (code "120") (name "Net-(VD4-A)") (class "Default")
      (node (ref "R67") (pin "2") (pinfunction "2_2") (pintype "passive"))
      (node (ref "VD4") (pin "2") (pinfunction "A_2") (pintype "passive"))
    )
    (net (code "121") (name "Net-(VT2-C)") (class "Default")
      (node (ref "R51") (pin "2") (pinfunction "2_2") (pintype "passive"))
      (node (ref "VT2") (pin "3") (pinfunction "C_3") (pintype "passive"))
    )
    (net (code "122") (name "Net-(XT4-FB)") (class "Default")
      (node (ref "R22") (pin "2") (pinfunction "2_2") (pintype "passive"))
      (node (ref "R23") (pin "1") (pinfunction "1_1") (pintype "passive"))
      (node (ref "XT4") (pin "3") (pinfunction "FB_3") (pintype "passive"))
    )
    (net (code "123") (name "VBAT") (class "Default")
      (node (ref "BT1") (pin "1") (pinfunction "+_1") (pintype "passive"))
      (node (ref "C9") (pin "1") (pinfunction "1_1") (pintype "passive"))
      (node (ref "R66") (pin "2") (pinfunction "2_2") (pintype "passive"))
      (node (ref "U1") (pin "1") (pinfunction "VBAT_1") (pintype "power_in"))
      (node (ref "VD4") (pin "1") (pinfunction "K_1") (pintype "passive"))
    )
    (net (code "124") (name "VBATI") (class "Default")
      (node (ref "C29") (pin "2") (pinfunction "2_2") (pintype "passive"))
      (node (ref "D2") (pin "3") (pinfunction "Vbat_3") (pintype "power_in"))
      (node (ref "SW10") (pin "2") (pinfunction "2_2") (pintype "passive"))
      (node (ref "X1") (pin "1") (pinfunction "1_1") (pintype "passive"))
    )
    (net (code "125") (name "VBATN") (class "Default")
      (node (ref "D7") (pin "3") (pinfunction "IN+_3") (pintype "passive"))
      (node (ref "R37") (pin "1") (pinfunction "1_1") (pintype "passive"))
      (node (ref "X2") (pin "1") (pinfunction "1_1") (pintype "passive"))
    )
    (net (code "126") (name "VBATO") (class "Default")
      (node (ref "C16") (pin "2") (pinfunction "2_2") (pintype "passive"))
      (node (ref "C17") (pin "2") (pinfunction "2_2") (pintype "passive"))
      (node (ref "J1") (pin "3") (pinfunction "3_3") (pintype "passive"))
      (node (ref "L1") (pin "1") (pinfunction "1_1") (pintype "passive"))
      (node (ref "R7") (pin "1") (pinfunction "1_1") (pintype "passive"))
      (node (ref "SW10") (pin "1") (pinfunction "1_1") (pintype "passive"))
      (node (ref "XT4") (pin "4") (pinfunction "EN_4") (pintype "passive"))
      (node (ref "XT4") (pin "5") (pinfunction "IN_5") (pintype "passive"))
    )
    (net (code "127") (name "VOUT") (class "Default")
      (node (ref "J1") (pin "2") (pinfunction "2_2") (pintype "passive"))
      (node (ref "XT1") (pin "1") (pinfunction "1_1") (pintype "passive"))
      (node (ref "XT3") (pin "1") (pinfunction "1_1") (pintype "passive"))
      (node (ref "XT6") (pin "1") (pinfunction "1_1") (pintype "passive"))
      (node (ref "XT7") (pin "1") (pinfunction "1_1") (pintype "passive"))
    )
    (net (code "128") (name "VUSB") (class "Default")
      (node (ref "C18") (pin "2") (pinfunction "2_2") (pintype "passive"))
      (node (ref "D1") (pin "1") (pinfunction "Vbus_1") (pintype "passive"))
      (node (ref "D2") (pin "4") (pinfunction "Vdd_4") (pintype "passive"))
      (node (ref "R10") (pin "1") (pinfunction "1_1") (pintype "passive"))
      (node (ref "R13") (pin "1") (pinfunction "1_1") (pintype "passive"))
      (node (ref "VD2") (pin "5") (pinfunction "VBUS_5") (pintype "passive"))
    )
    (net (code "129") (name "unconnected-(D1-OTG-Pad4)") (class "Default")
      (node (ref "D1") (pin "4") (pinfunction "OTG_4") (pintype "passive+no_connect"))
    )
    (net (code "130") (name "unconnected-(D3B-2OUT-Pad7)") (class "Default")
      (node (ref "D3") (pin "7") (pinfunction "2OUT_7") (pintype "passive+no_connect"))
    )
    (net (code "131") (name "unconnected-(DA2-DNC-Pad8)") (class "Default")
      (node (ref "DA2") (pin "8") (pinfunction "DNC_8") (pintype "passive+no_connect"))
    )
    (net (code "132") (name "unconnected-(DA3-AUX_CL-Pad7)") (class "Default")
      (node (ref "DA3") (pin "7") (pinfunction "AUX_CL_7") (pintype "passive"))
    )
    (net (code "133") (name "unconnected-(DA3-AUX_DA-Pad6)") (class "Default")
      (node (ref "DA3") (pin "6") (pinfunction "AUX_DA_6") (pintype "passive"))
    )
    (net (code "134") (name "unconnected-(DA3-RESV-Pad19)") (class "Default")
      (node (ref "DA3") (pin "19") (pinfunction "RESV_19") (pintype "passive"))
    )
    (net (code "135") (name "unconnected-(DA3-RESV-Pad21)") (class "Default")
      (node (ref "DA3") (pin "21") (pinfunction "RESV_21") (pintype "passive"))
    )
    (net (code "136") (name "unconnected-(DA3-RESV-Pad22)") (class "Default")
      (node (ref "DA3") (pin "22") (pinfunction "RESV_22") (pintype "passive"))
    )
    (net (code "137") (name "unconnected-(H1-D3-Pad21)") (class "Default")
      (node (ref "H1") (pin "21") (pinfunction "D3_21") (pintype "passive+no_connect"))
    )
    (net (code "138") (name "unconnected-(H1-D4-Pad22)") (class "Default")
      (node (ref "H1") (pin "22") (pinfunction "D4_22") (pintype "passive+no_connect"))
    )
    (net (code "139") (name "unconnected-(H1-D5-Pad23)") (class "Default")
      (node (ref "H1") (pin "23") (pinfunction "D5_23") (pintype "passive+no_connect"))
    )
    (net (code "140") (name "unconnected-(H1-D6-Pad24)") (class "Default")
      (node (ref "H1") (pin "24") (pinfunction "D6_24") (pintype "passive+no_connect"))
    )
    (net (code "141") (name "unconnected-(H1-D7-Pad25)") (class "Default")
      (node (ref "H1") (pin "25") (pinfunction "D7_25") (pintype "passive+no_connect"))
    )
    (net (code "142") (name "unconnected-(H1-E{slash}RD#-Pad17)") (class "Default")
      (node (ref "H1") (pin "17") (pinfunction "E/RD#_17") (pintype "passive+no_connect"))
    )
    (net (code "143") (name "unconnected-(H1-NC-Pad7)") (class "Default")
      (node (ref "H1") (pin "7") (pinfunction "NC_7") (pintype "passive+no_connect"))
    )
    (net (code "144") (name "unconnected-(H1-R{slash}W#-Pad16)") (class "Default")
      (node (ref "H1") (pin "16") (pinfunction "R/W#_16") (pintype "passive+no_connect"))
    )
    (net (code "145") (name "unconnected-(HL5-Dout-Pad2)") (class "Default")
      (node (ref "HL5") (pin "2") (pinfunction "Dout_2") (pintype "passive+no_connect"))
    )
    (net (code "146") (name "unconnected-(SW10-Pad3)") (class "Default")
      (node (ref "SW10") (pin "3") (pinfunction "3_3") (pintype "passive+no_connect"))
    )
    (net (code "147") (name "unconnected-(U1-PA0-WKUP-Pad14)") (class "Default")
      (node (ref "U1") (pin "14") (pinfunction "PA0-WKUP_14") (pintype "bidirectional"))
    )
    (net (code "148") (name "unconnected-(U1-PC13-TAMPER-RTC-Pad2)") (class "Default")
      (node (ref "U1") (pin "2") (pinfunction "PC13-TAMPER-RTC_2") (pintype "bidirectional+no_connect"))
    )
    (net (code "149") (name "unconnected-(XT4-NC-Pad6)") (class "Default")
      (node (ref "XT4") (pin "6") (pinfunction "NC_6") (pintype "passive+no_connect"))
    )
  )
)
